# PT_2015_PB_MAIN_Rev2.net
KiCad netlist of a schematic drawn in EAGLE
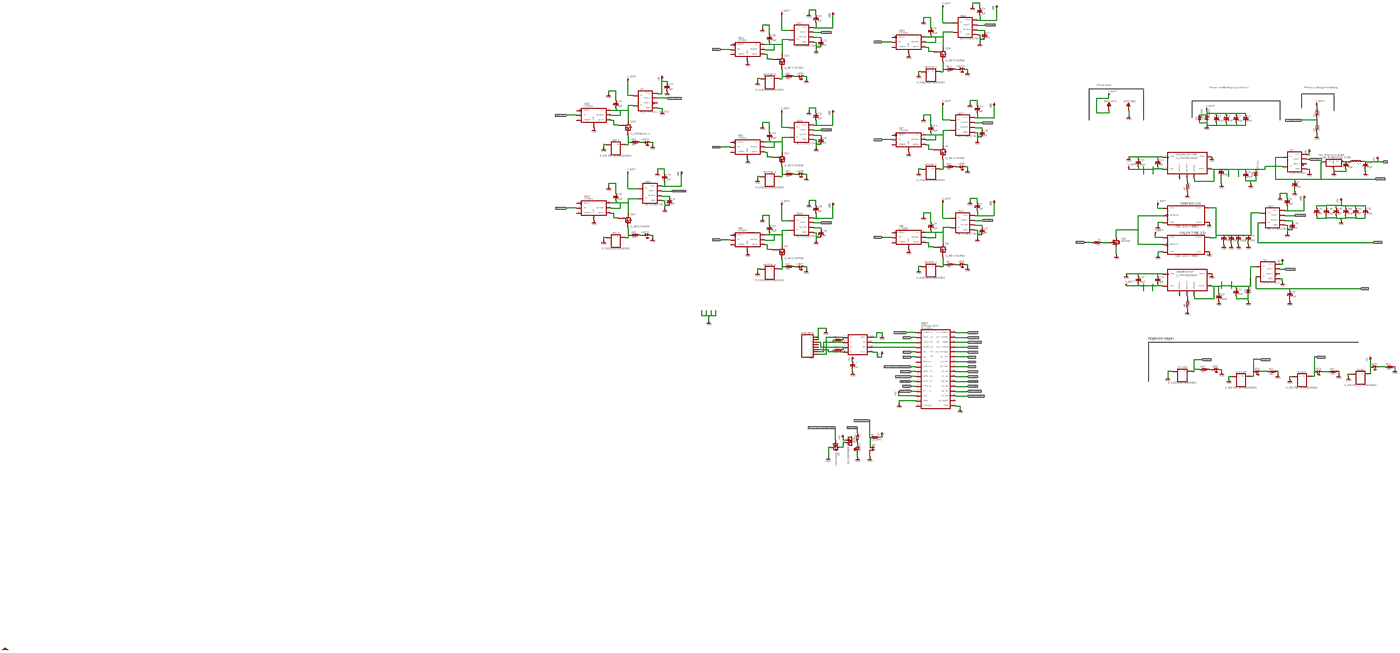
[diagram p0: schematic, sheet 1, overview]
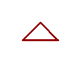
[diagram p1: schematic, sheet 1, part 1 of 5]
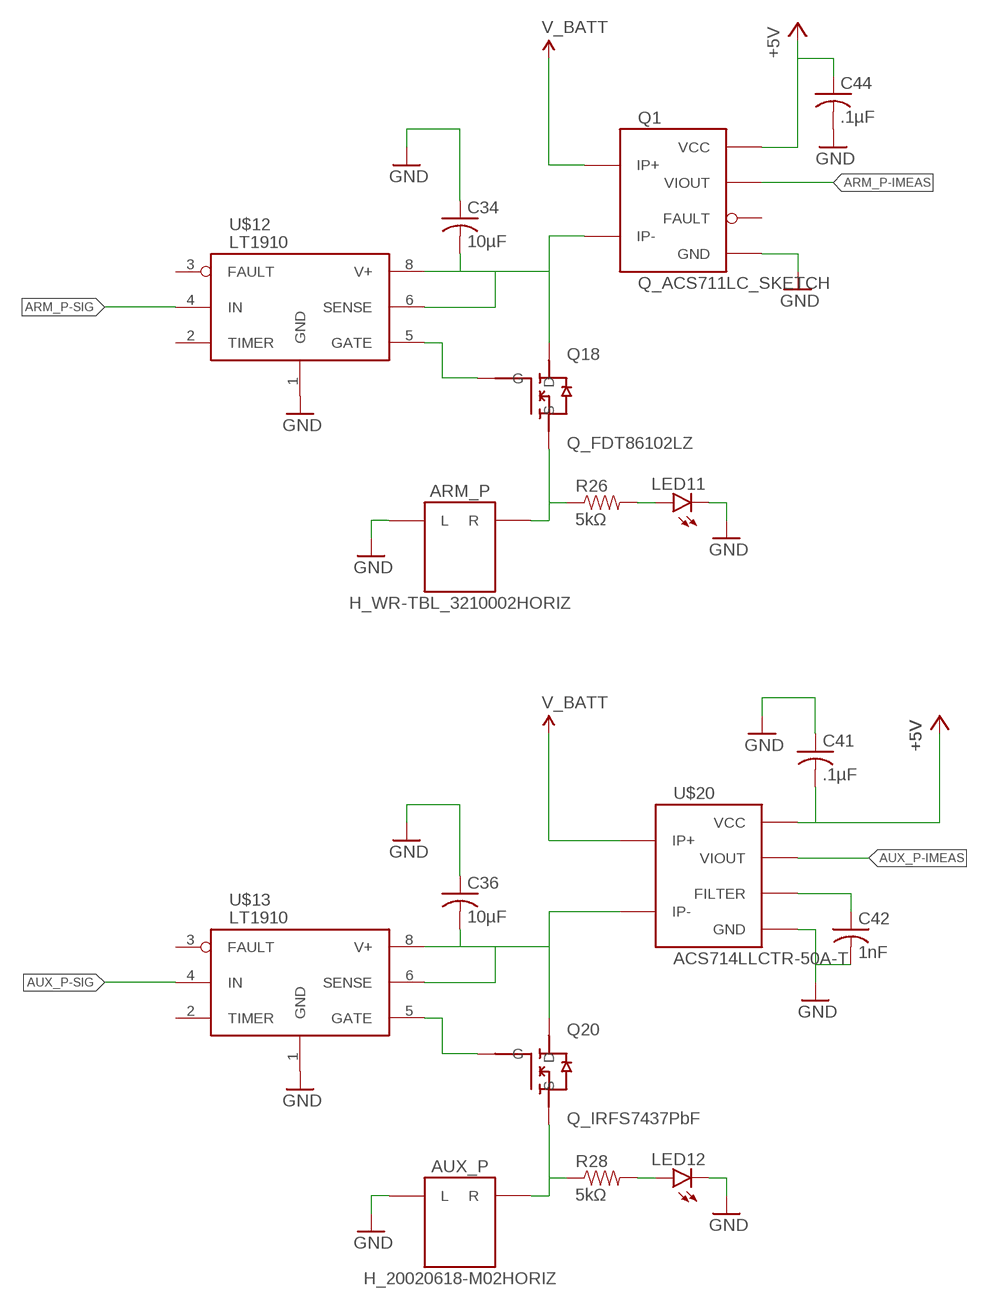
[diagram p2: schematic, sheet 1, part 2 of 5]
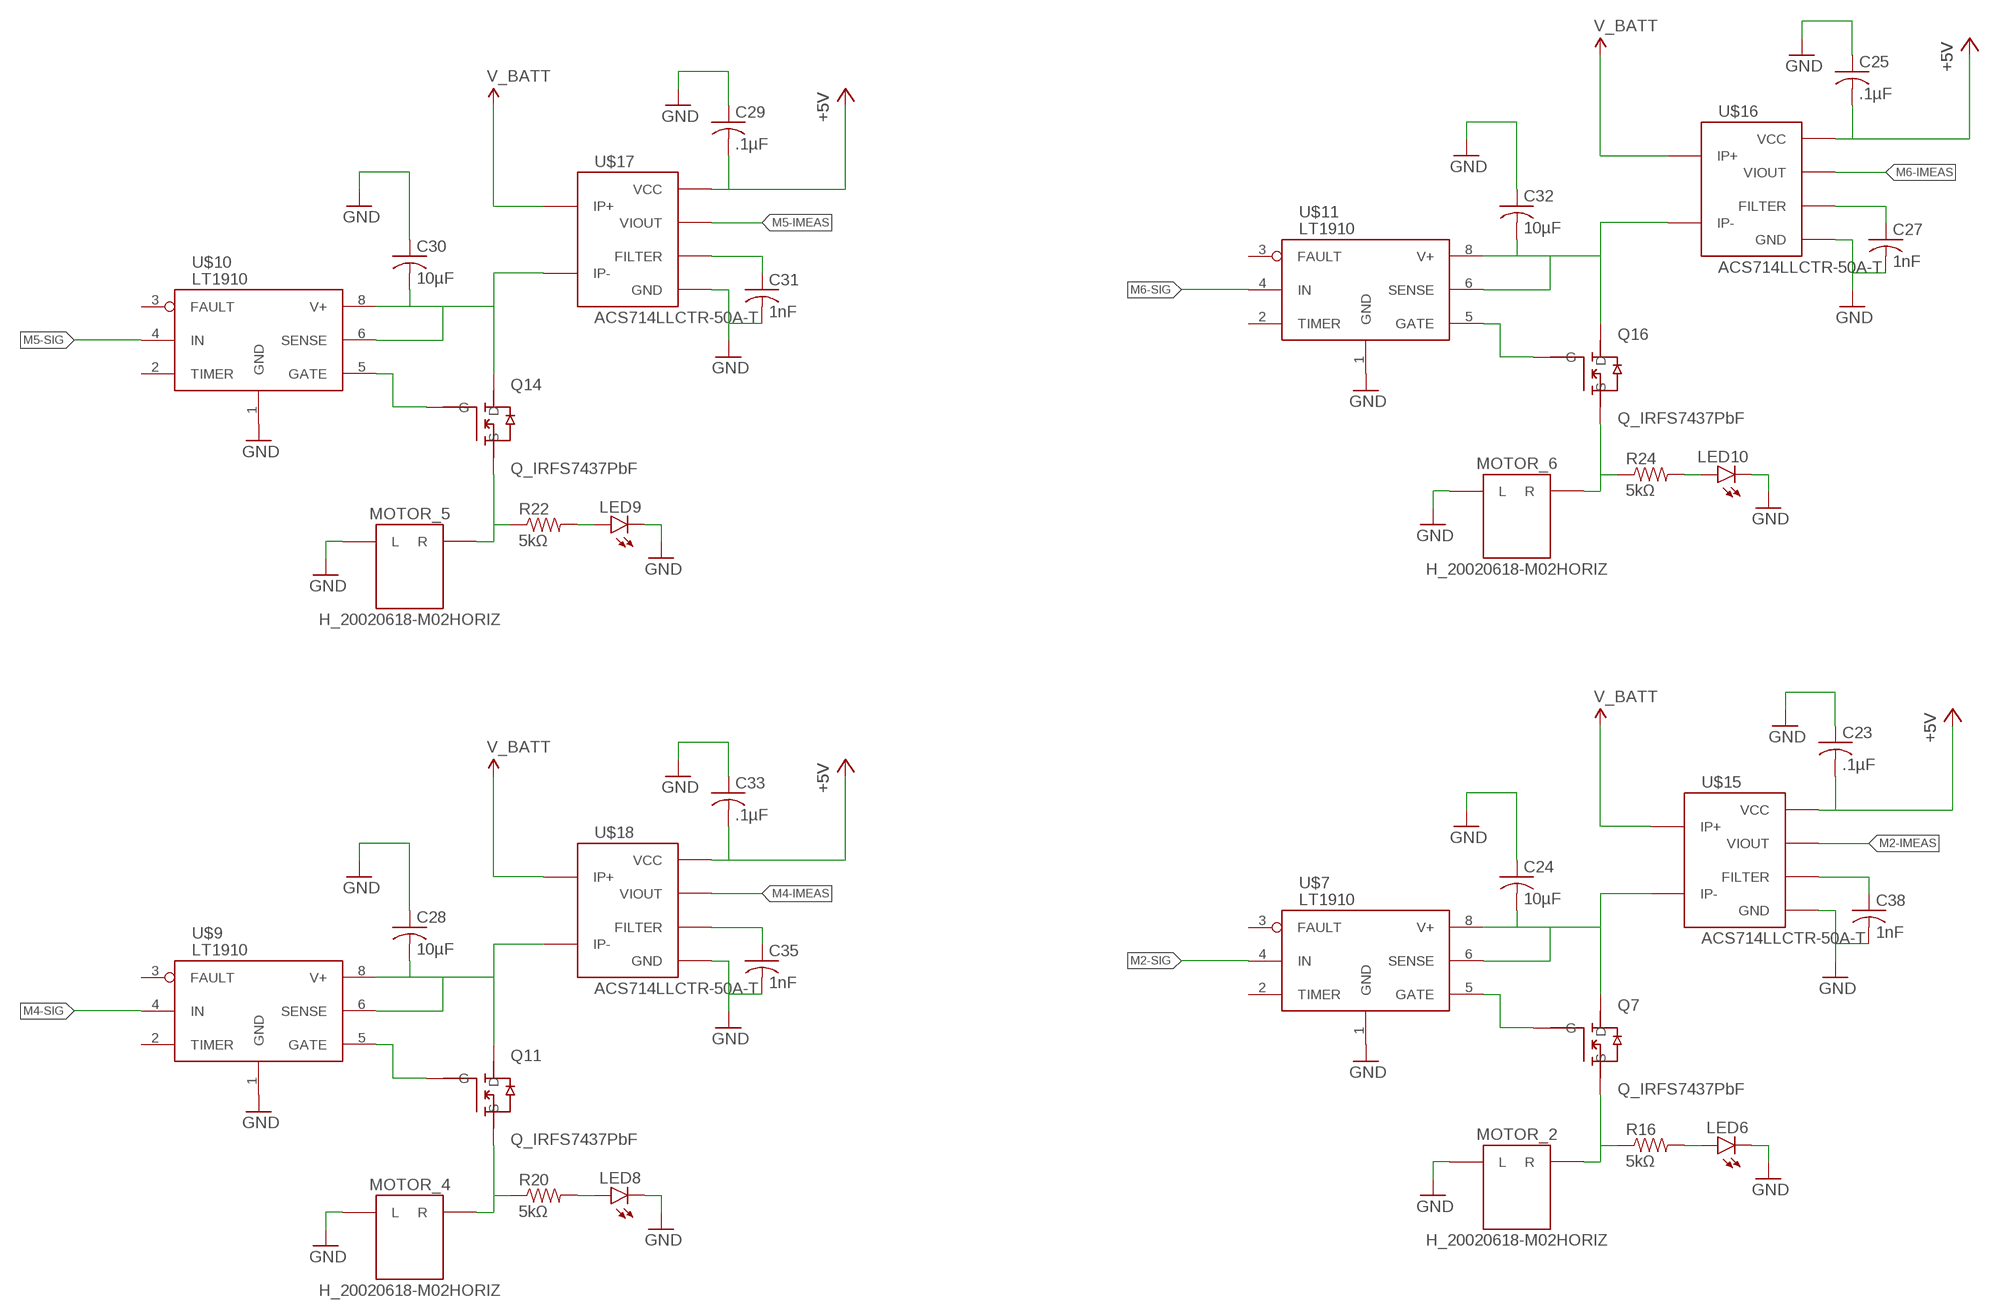
[diagram p3: schematic, sheet 1, part 3 of 5]
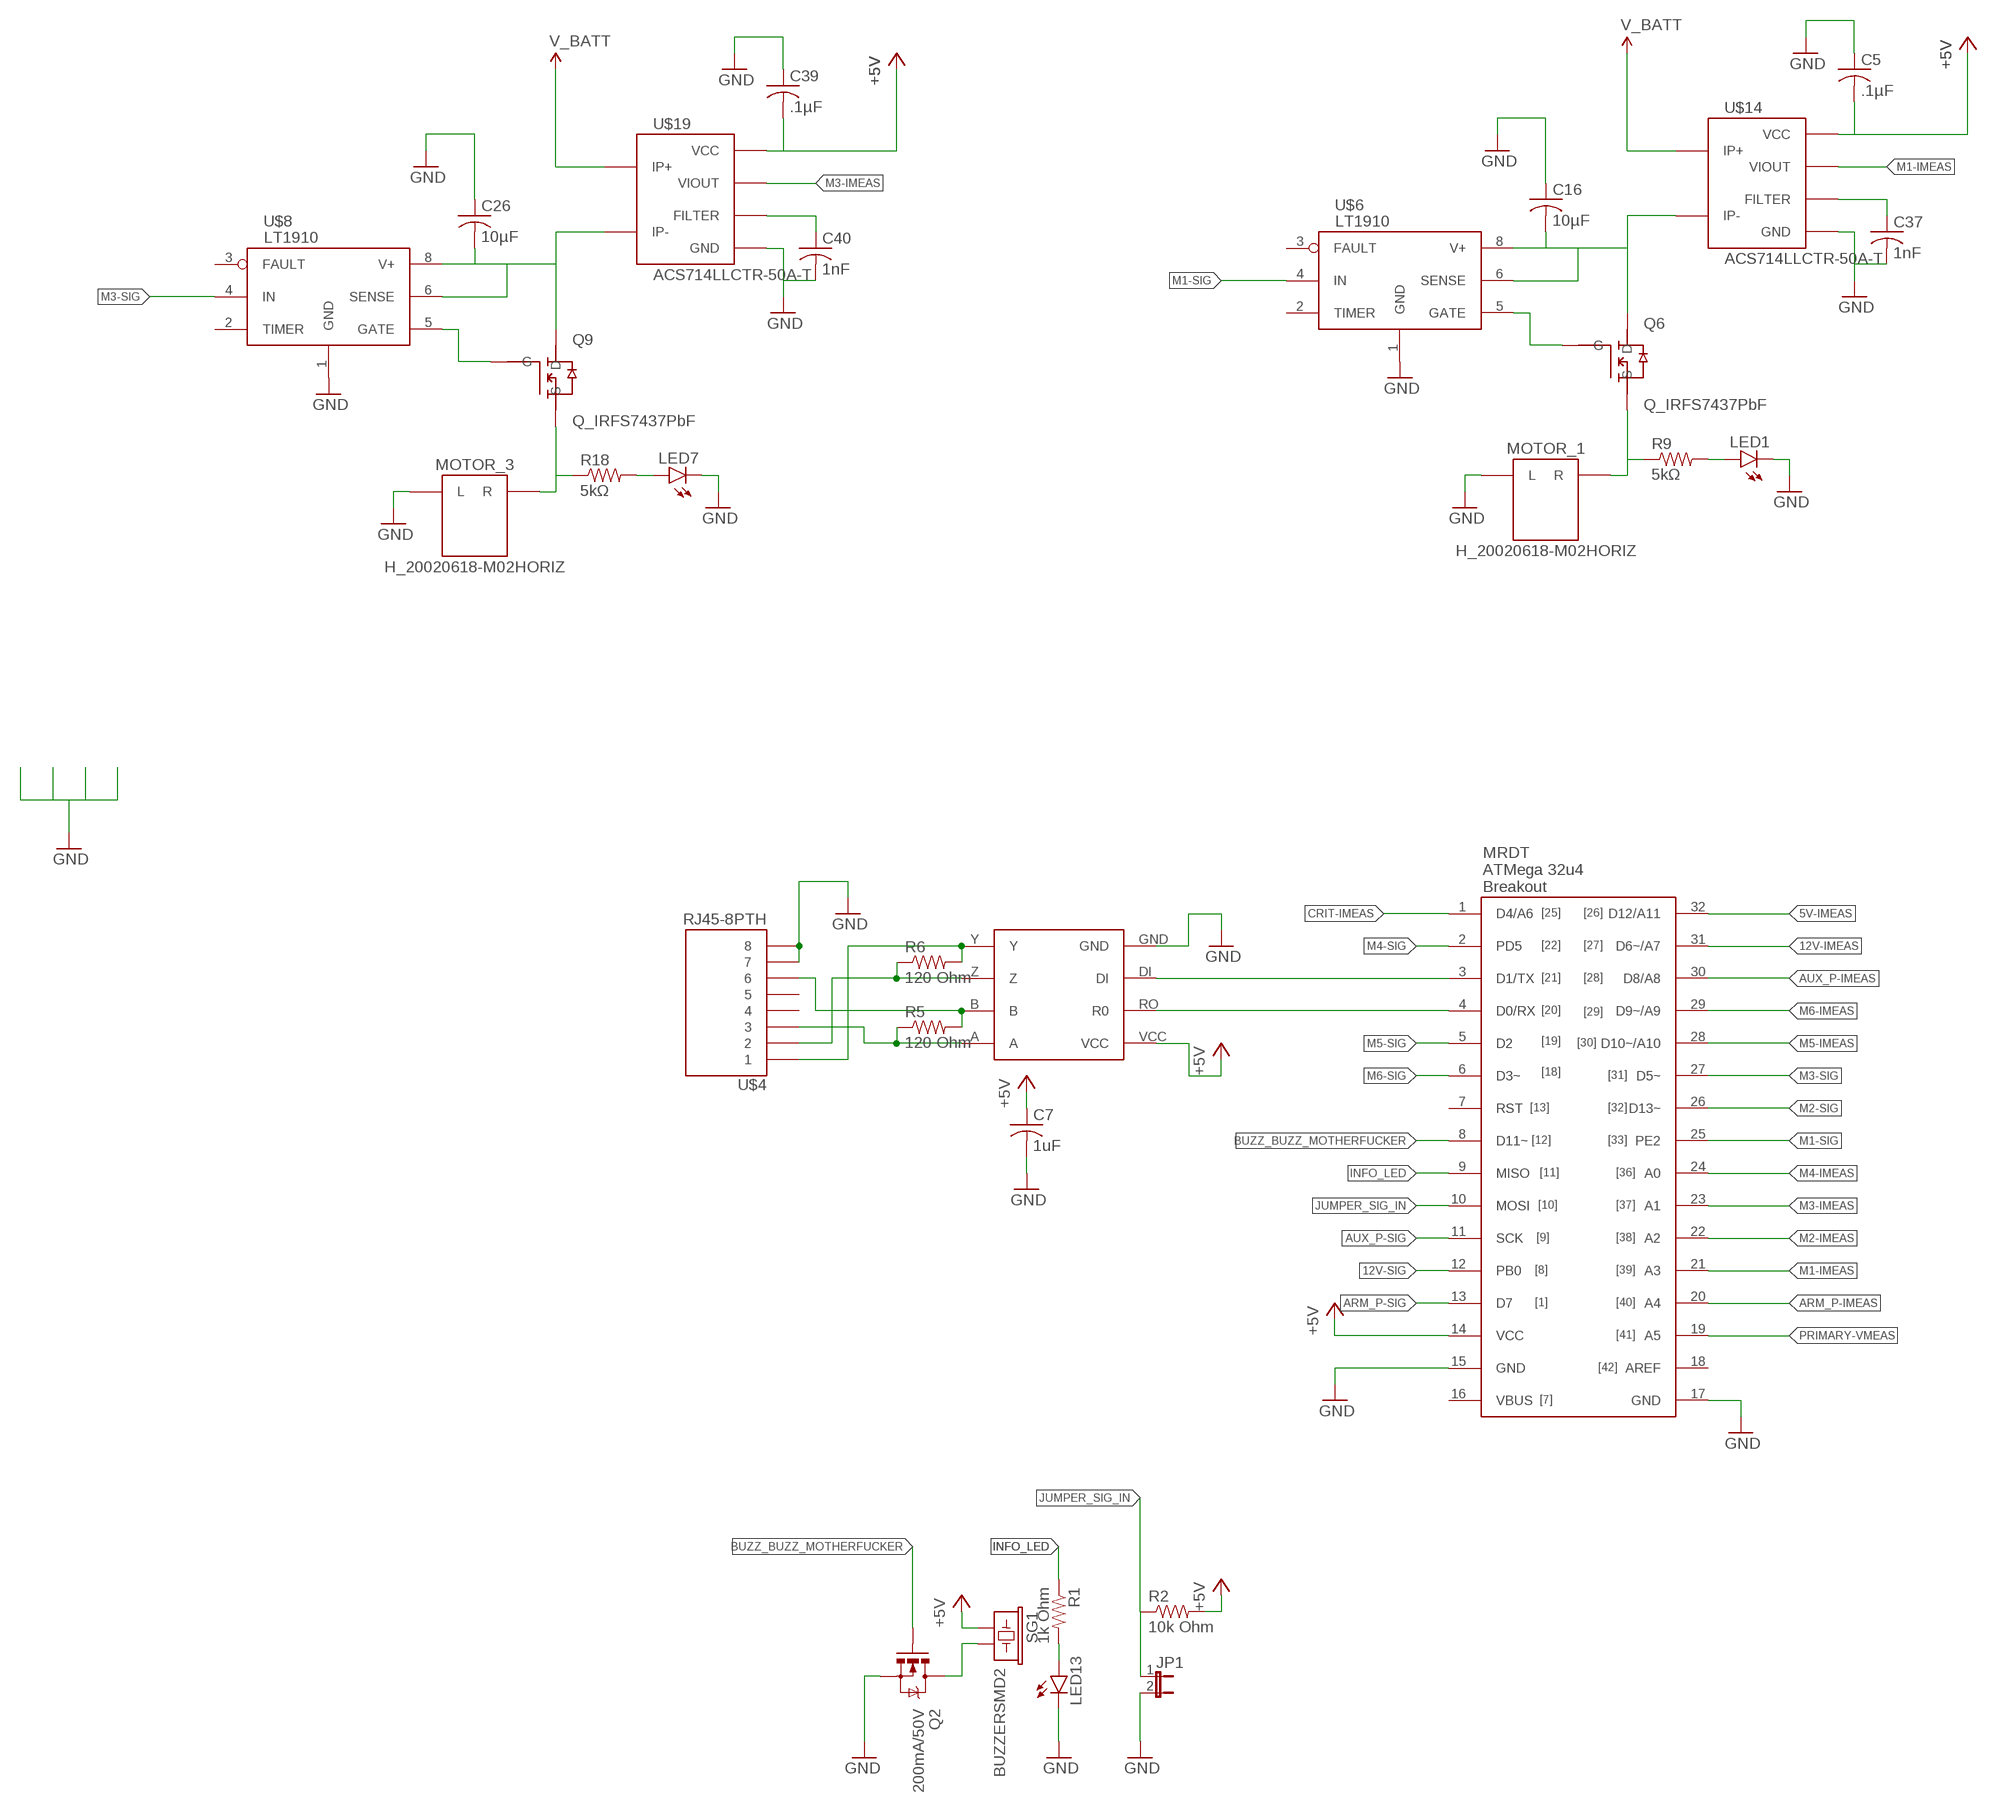
[diagram p4: schematic, sheet 1, part 4 of 5]
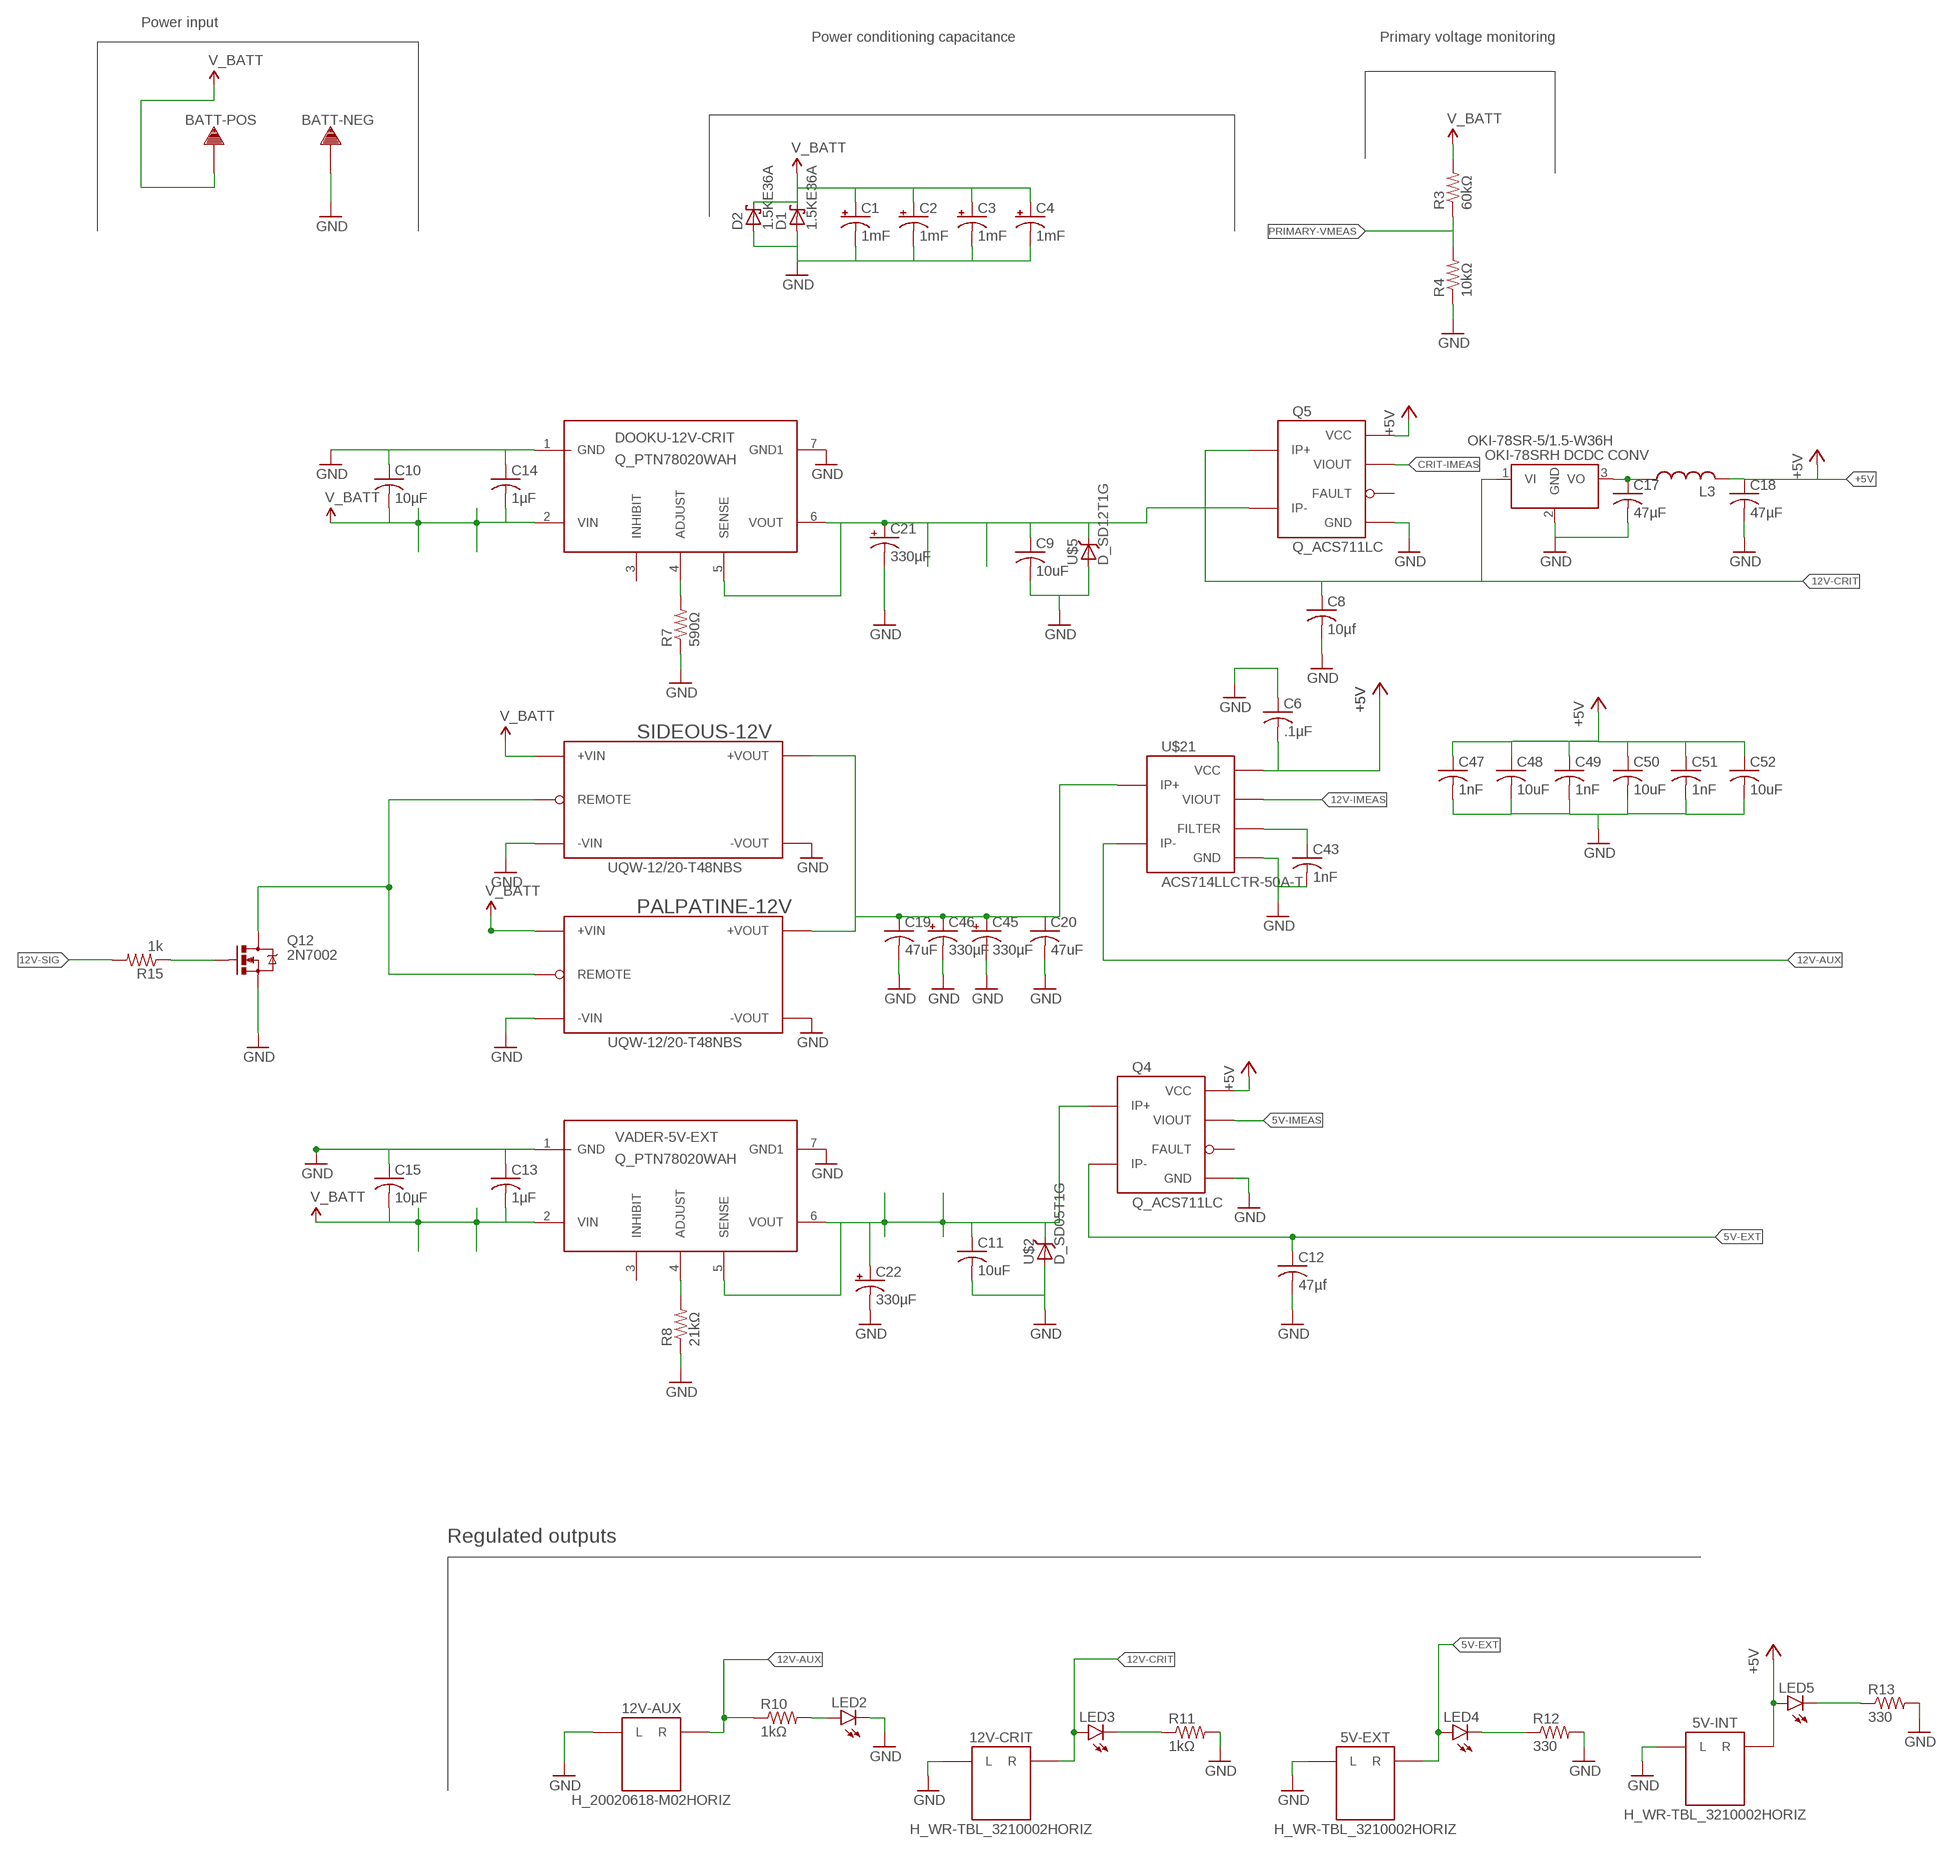
[diagram p5: schematic, sheet 1, part 5 of 5]

(export (version "E")
  (design (tool "Eeschema 10.0.6"))
  (components
    (comp (ref "5V-EXT")
      (value "H_WR-TBL_3210002HORIZ")
      (footprint "eagle-import:691322110002")
      (libsource (lib "eagle-import") (part "H_WR-TBL_3210002HORIZ"))
    )
    (comp (ref "5V-INT")
      (value "H_WR-TBL_3210002HORIZ")
      (footprint "eagle-import:691322110002")
      (libsource (lib "eagle-import") (part "H_WR-TBL_3210002HORIZ"))
    )
    (comp (ref "12V-AUX")
      (value "H_20020618-M02HORIZ")
      (footprint "eagle-import:20020618-M02")
      (libsource (lib "eagle-import") (part "H_20020618-M02HORIZ"))
    )
    (comp (ref "12V-CRIT")
      (value "H_WR-TBL_3210002HORIZ")
      (footprint "eagle-import:691322110002")
      (libsource (lib "eagle-import") (part "H_WR-TBL_3210002HORIZ"))
    )
    (comp (ref "ARM_P")
      (value "H_WR-TBL_3210002HORIZ")
      (footprint "eagle-import:691322110002")
      (libsource (lib "eagle-import") (part "H_WR-TBL_3210002HORIZ"))
    )
    (comp (ref "AUX_P")
      (value "H_20020618-M02HORIZ")
      (footprint "eagle-import:20020618-M02")
      (libsource (lib "eagle-import") (part "H_20020618-M02HORIZ"))
    )
    (comp (ref "BATT-NEG")
      (value "TERMINAL_HOLE")
      (footprint "eagle-import:LARGE_TERMINAL_HOLE")
      (libsource (lib "eagle-import") (part "TERMINAL_HOLE"))
    )
    (comp (ref "BATT-POS")
      (value "TERMINAL_HOLE")
      (footprint "eagle-import:LARGE_TERMINAL_HOLE")
      (libsource (lib "eagle-import") (part "TERMINAL_HOLE"))
    )
    (comp (ref "C1")
      (value "1mF")
      (footprint "eagle-import:C_12.5MM")
      (libsource (lib "eagle-import") (part "C_POL12.5MM_NORMAL"))
    )
    (comp (ref "C2")
      (value "1mF")
      (footprint "eagle-import:C_12.5MM")
      (libsource (lib "eagle-import") (part "C_POL12.5MM_NORMAL"))
    )
    (comp (ref "C3")
      (value "1mF")
      (footprint "eagle-import:C_12.5MM")
      (libsource (lib "eagle-import") (part "C_POL12.5MM_NORMAL"))
    )
    (comp (ref "C4")
      (value "1mF")
      (footprint "eagle-import:C_12.5MM")
      (libsource (lib "eagle-import") (part "C_POL12.5MM_NORMAL"))
    )
    (comp (ref "C5")
      (value ".1µF")
      (footprint "eagle-import:C1206")
      (libsource (lib "eagle-import") (part "C-USC1206"))
    )
    (comp (ref "C6")
      (value ".1µF")
      (footprint "eagle-import:C1206")
      (libsource (lib "eagle-import") (part "C-USC1206"))
    )
    (comp (ref "C7")
      (value "1uF")
      (footprint "eagle-import:C1206")
      (libsource (lib "eagle-import") (part "C-USC1206"))
    )
    (comp (ref "C8")
      (value "10µf")
      (footprint "eagle-import:C1206")
      (libsource (lib "eagle-import") (part "C-USC1206"))
    )
    (comp (ref "C9")
      (value "10uF")
      (footprint "eagle-import:C1206")
      (libsource (lib "eagle-import") (part "C-USC1206"))
    )
    (comp (ref "C10")
      (value "10µF")
      (footprint "eagle-import:C1206")
      (libsource (lib "eagle-import") (part "C-USC1206"))
    )
    (comp (ref "C11")
      (value "10uF")
      (footprint "eagle-import:C1206")
      (libsource (lib "eagle-import") (part "C-USC1206"))
    )
    (comp (ref "C12")
      (value "47µf")
      (footprint "eagle-import:C1206")
      (libsource (lib "eagle-import") (part "C-USC1206"))
    )
    (comp (ref "C13")
      (value "1µF")
      (footprint "eagle-import:C1206")
      (libsource (lib "eagle-import") (part "C-USC1206"))
    )
    (comp (ref "C14")
      (value "1µF")
      (footprint "eagle-import:C1206")
      (libsource (lib "eagle-import") (part "C-USC1206"))
    )
    (comp (ref "C15")
      (value "10µF")
      (footprint "eagle-import:C1206")
      (libsource (lib "eagle-import") (part "C-USC1206"))
    )
    (comp (ref "C16")
      (value "10µF")
      (footprint "eagle-import:C1206")
      (libsource (lib "eagle-import") (part "C-USC1206"))
    )
    (comp (ref "C17")
      (value "47µF")
      (footprint "eagle-import:C1206")
      (libsource (lib "eagle-import") (part "C-USC1206"))
    )
    (comp (ref "C18")
      (value "47µF")
      (footprint "eagle-import:C1206")
      (libsource (lib "eagle-import") (part "C-USC1206"))
    )
    (comp (ref "C19")
      (value "47uF")
      (footprint "eagle-import:C1206")
      (libsource (lib "eagle-import") (part "C-USC1206"))
    )
    (comp (ref "C20")
      (value "47uF")
      (footprint "eagle-import:C1206")
      (libsource (lib "eagle-import") (part "C-USC1206"))
    )
    (comp (ref "C21")
      (value "330µF")
      (footprint "eagle-import:E5-8,5")
      (libsource (lib "eagle-import") (part "CPOL-USE5-8.5"))
    )
    (comp (ref "C22")
      (value "330µF")
      (footprint "eagle-import:E5-8,5")
      (libsource (lib "eagle-import") (part "CPOL-USE5-8.5"))
    )
    (comp (ref "C23")
      (value ".1µF")
      (footprint "eagle-import:C1206")
      (libsource (lib "eagle-import") (part "C-USC1206"))
    )
    (comp (ref "C24")
      (value "10µF")
      (footprint "eagle-import:C1206")
      (libsource (lib "eagle-import") (part "C-USC1206"))
    )
    (comp (ref "C25")
      (value ".1µF")
      (footprint "eagle-import:C1206")
      (libsource (lib "eagle-import") (part "C-USC1206"))
    )
    (comp (ref "C26")
      (value "10µF")
      (footprint "eagle-import:C1206")
      (libsource (lib "eagle-import") (part "C-USC1206"))
    )
    (comp (ref "C27")
      (value "1nF")
      (footprint "eagle-import:C1206")
      (libsource (lib "eagle-import") (part "C-USC1206"))
    )
    (comp (ref "C28")
      (value "10µF")
      (footprint "eagle-import:C1206")
      (libsource (lib "eagle-import") (part "C-USC1206"))
    )
    (comp (ref "C29")
      (value ".1µF")
      (footprint "eagle-import:C1206")
      (libsource (lib "eagle-import") (part "C-USC1206"))
    )
    (comp (ref "C30")
      (value "10µF")
      (footprint "eagle-import:C1206")
      (libsource (lib "eagle-import") (part "C-USC1206"))
    )
    (comp (ref "C31")
      (value "1nF")
      (footprint "eagle-import:C1206")
      (libsource (lib "eagle-import") (part "C-USC1206"))
    )
    (comp (ref "C32")
      (value "10µF")
      (footprint "eagle-import:C1206")
      (libsource (lib "eagle-import") (part "C-USC1206"))
    )
    (comp (ref "C33")
      (value ".1µF")
      (footprint "eagle-import:C1206")
      (libsource (lib "eagle-import") (part "C-USC1206"))
    )
    (comp (ref "C34")
      (value "10µF")
      (footprint "eagle-import:C1206")
      (libsource (lib "eagle-import") (part "C-USC1206"))
    )
    (comp (ref "C35")
      (value "1nF")
      (footprint "eagle-import:C1206")
      (libsource (lib "eagle-import") (part "C-USC1206"))
    )
    (comp (ref "C36")
      (value "10µF")
      (footprint "eagle-import:C1206")
      (libsource (lib "eagle-import") (part "C-USC1206"))
    )
    (comp (ref "C37")
      (value "1nF")
      (footprint "eagle-import:C1206")
      (libsource (lib "eagle-import") (part "C-USC1206"))
    )
    (comp (ref "C38")
      (value "1nF")
      (footprint "eagle-import:C1206")
      (libsource (lib "eagle-import") (part "C-USC1206"))
    )
    (comp (ref "C39")
      (value ".1µF")
      (footprint "eagle-import:C1206")
      (libsource (lib "eagle-import") (part "C-USC1206"))
    )
    (comp (ref "C40")
      (value "1nF")
      (footprint "eagle-import:C1206")
      (libsource (lib "eagle-import") (part "C-USC1206"))
    )
    (comp (ref "C41")
      (value ".1µF")
      (footprint "eagle-import:C1206")
      (libsource (lib "eagle-import") (part "C-USC1206"))
    )
    (comp (ref "C42")
      (value "1nF")
      (footprint "eagle-import:C1206")
      (libsource (lib "eagle-import") (part "C-USC1206"))
    )
    (comp (ref "C43")
      (value "1nF")
      (footprint "eagle-import:C1206")
      (libsource (lib "eagle-import") (part "C-USC1206"))
    )
    (comp (ref "C44")
      (value ".1µF")
      (footprint "eagle-import:C1206")
      (libsource (lib "eagle-import") (part "C-USC1206"))
    )
    (comp (ref "C45")
      (value "330µF")
      (footprint "eagle-import:E5-8,5")
      (libsource (lib "eagle-import") (part "CPOL-USE5-8.5"))
    )
    (comp (ref "C46")
      (value "330µF")
      (footprint "eagle-import:E5-8,5")
      (libsource (lib "eagle-import") (part "CPOL-USE5-8.5"))
    )
    (comp (ref "C47")
      (value "1nF")
      (footprint "eagle-import:C1206")
      (libsource (lib "eagle-import") (part "C-USC1206"))
    )
    (comp (ref "C48")
      (value "10uF")
      (footprint "eagle-import:C1206")
      (libsource (lib "eagle-import") (part "C-USC1206"))
    )
    (comp (ref "C49")
      (value "1nF")
      (footprint "eagle-import:C1206")
      (libsource (lib "eagle-import") (part "C-USC1206"))
    )
    (comp (ref "C50")
      (value "10uF")
      (footprint "eagle-import:C1206")
      (libsource (lib "eagle-import") (part "C-USC1206"))
    )
    (comp (ref "C51")
      (value "1nF")
      (footprint "eagle-import:C1206")
      (libsource (lib "eagle-import") (part "C-USC1206"))
    )
    (comp (ref "C52")
      (value "10uF")
      (footprint "eagle-import:C1206")
      (libsource (lib "eagle-import") (part "C-USC1206"))
    )
    (comp (ref "D1")
      (value "1.5KE36A")
      (footprint "eagle-import:CB429-17")
      (libsource (lib "eagle-import") (part "15KEXX"))
    )
    (comp (ref "D2")
      (value "1.5KE36A")
      (footprint "eagle-import:CB429-17")
      (libsource (lib "eagle-import") (part "15KEXX"))
    )
    (comp (ref "DOOKU-12V-CRIT")
      (value "Q_PTN78020WAH")
      (footprint "eagle-import:R_PDSS-T7")
      (libsource (lib "eagle-import") (part "Q_PTN78020"))
    )
    (comp (ref "JP1")
      (value "JP1E")
      (footprint "eagle-import:JP1")
      (libsource (lib "eagle-import") (part "JP1E"))
    )
    (comp (ref "L3")
      (value "L-USL8530M")
      (footprint "eagle-import:L8530M")
      (libsource (lib "eagle-import") (part "L-USL8530M"))
    )
    (comp (ref "LED1")
      (value "LED1206")
      (footprint "eagle-import:LED-1206")
      (libsource (lib "eagle-import") (part "LED1206"))
    )
    (comp (ref "LED2")
      (value "LED1206")
      (footprint "eagle-import:LED-1206")
      (libsource (lib "eagle-import") (part "LED1206"))
    )
    (comp (ref "LED3")
      (value "LED1206")
      (footprint "eagle-import:LED-1206")
      (libsource (lib "eagle-import") (part "LED1206"))
    )
    (comp (ref "LED4")
      (value "LED1206")
      (footprint "eagle-import:LED-1206")
      (libsource (lib "eagle-import") (part "LED1206"))
    )
    (comp (ref "LED5")
      (value "LED1206")
      (footprint "eagle-import:LED-1206")
      (libsource (lib "eagle-import") (part "LED1206"))
    )
    (comp (ref "LED6")
      (value "LED1206")
      (footprint "eagle-import:LED-1206")
      (libsource (lib "eagle-import") (part "LED1206"))
    )
    (comp (ref "LED7")
      (value "LED1206")
      (footprint "eagle-import:LED-1206")
      (libsource (lib "eagle-import") (part "LED1206"))
    )
    (comp (ref "LED8")
      (value "LED1206")
      (footprint "eagle-import:LED-1206")
      (libsource (lib "eagle-import") (part "LED1206"))
    )
    (comp (ref "LED9")
      (value "LED1206")
      (footprint "eagle-import:LED-1206")
      (libsource (lib "eagle-import") (part "LED1206"))
    )
    (comp (ref "LED10")
      (value "LED1206")
      (footprint "eagle-import:LED-1206")
      (libsource (lib "eagle-import") (part "LED1206"))
    )
    (comp (ref "LED11")
      (value "LED1206")
      (footprint "eagle-import:LED-1206")
      (libsource (lib "eagle-import") (part "LED1206"))
    )
    (comp (ref "LED12")
      (value "LED1206")
      (footprint "eagle-import:LED-1206")
      (libsource (lib "eagle-import") (part "LED1206"))
    )
    (comp (ref "LED13")
      (value "LED-FKIT-1206")
      (footprint "eagle-import:FKIT-LED-1206")
      (libsource (lib "eagle-import") (part "LED-FKIT-1206"))
    )
    (comp (ref "MOTOR_1")
      (value "H_20020618-M02HORIZ")
      (footprint "eagle-import:20020618-M02")
      (libsource (lib "eagle-import") (part "H_20020618-M02HORIZ"))
    )
    (comp (ref "MOTOR_2")
      (value "H_20020618-M02HORIZ")
      (footprint "eagle-import:20020618-M02")
      (libsource (lib "eagle-import") (part "H_20020618-M02HORIZ"))
    )
    (comp (ref "MOTOR_3")
      (value "H_20020618-M02HORIZ")
      (footprint "eagle-import:20020618-M02")
      (libsource (lib "eagle-import") (part "H_20020618-M02HORIZ"))
    )
    (comp (ref "MOTOR_4")
      (value "H_20020618-M02HORIZ")
      (footprint "eagle-import:20020618-M02")
      (libsource (lib "eagle-import") (part "H_20020618-M02HORIZ"))
    )
    (comp (ref "MOTOR_5")
      (value "H_20020618-M02HORIZ")
      (footprint "eagle-import:20020618-M02")
      (libsource (lib "eagle-import") (part "H_20020618-M02HORIZ"))
    )
    (comp (ref "MOTOR_6")
      (value "H_20020618-M02HORIZ")
      (footprint "eagle-import:20020618-M02")
      (libsource (lib "eagle-import") (part "H_20020618-M02HORIZ"))
    )
    (comp (ref "OKI-78SR-5/1.5-W36H")
      (value "Q_OKI-78SR")
      (footprint "eagle-import:OKI-78SRH")
      (libsource (lib "eagle-import") (part "Q_OKI-78SR"))
    )
    (comp (ref "PALPATINE-12V")
      (value "UQW-12/20-T48NBS")
      (footprint "eagle-import:U-T48-QB-NO_TRIM")
      (libsource (lib "eagle-import") (part "UQW-12/20-T48NBS"))
    )
    (comp (ref "Q1")
      (value "Q_ACS711LC_SKETCH")
      (footprint "eagle-import:SOIC8_ACS711_SKETCH")
      (libsource (lib "eagle-import") (part "Q_ACS711LC_SKETCH"))
    )
    (comp (ref "Q2")
      (value "200mA/50V")
      (footprint "eagle-import:SOT23-3")
      (libsource (lib "eagle-import") (part "MOSFET-NCHANNELBSS138"))
    )
    (comp (ref "Q4")
      (value "Q_ACS711LC")
      (footprint "eagle-import:SOIC8_ACS711")
      (libsource (lib "eagle-import") (part "Q_ACS711LC"))
    )
    (comp (ref "Q5")
      (value "Q_ACS711LC")
      (footprint "eagle-import:SOIC8_ACS711")
      (libsource (lib "eagle-import") (part "Q_ACS711LC"))
    )
    (comp (ref "Q6")
      (value "Q_IRFS7437PbF")
      (footprint "eagle-import:D2PACK")
      (libsource (lib "eagle-import") (part "Q_IRF7437SMD"))
    )
    (comp (ref "Q7")
      (value "Q_IRFS7437PbF")
      (footprint "eagle-import:D2PACK")
      (libsource (lib "eagle-import") (part "Q_IRF7437SMD"))
    )
    (comp (ref "Q9")
      (value "Q_IRFS7437PbF")
      (footprint "eagle-import:D2PACK")
      (libsource (lib "eagle-import") (part "Q_IRF7437SMD"))
    )
    (comp (ref "Q11")
      (value "Q_IRFS7437PbF")
      (footprint "eagle-import:D2PACK")
      (libsource (lib "eagle-import") (part "Q_IRF7437SMD"))
    )
    (comp (ref "Q12")
      (value "2N7002")
      (footprint "eagle-import:SOT323")
      (libsource (lib "eagle-import") (part "MOSFET-NCHANNEL2N7002PW"))
    )
    (comp (ref "Q14")
      (value "Q_IRFS7437PbF")
      (footprint "eagle-import:D2PACK")
      (libsource (lib "eagle-import") (part "Q_IRF7437SMD"))
    )
    (comp (ref "Q16")
      (value "Q_IRFS7437PbF")
      (footprint "eagle-import:D2PACK")
      (libsource (lib "eagle-import") (part "Q_IRF7437SMD"))
    )
    (comp (ref "Q18")
      (value "Q_FDT86102LZ")
      (footprint "eagle-import:SOT-223")
      (libsource (lib "eagle-import") (part "Q_FDT86102LZ"))
    )
    (comp (ref "Q20")
      (value "Q_IRFS7437PbF")
      (footprint "eagle-import:D2PACK")
      (libsource (lib "eagle-import") (part "Q_IRF7437SMD"))
    )
    (comp (ref "R1")
      (value "1k Ohm")
      (footprint "eagle-import:1206")
      (libsource (lib "eagle-import") (part "RESISTOR1206"))
    )
    (comp (ref "R2")
      (value "10k Ohm")
      (footprint "eagle-import:1206")
      (libsource (lib "eagle-import") (part "RESISTOR1206"))
    )
    (comp (ref "R3")
      (value "60kΩ")
      (footprint "eagle-import:R1206")
      (libsource (lib "eagle-import") (part "R-US_R1206"))
    )
    (comp (ref "R4")
      (value "10kΩ")
      (footprint "eagle-import:R1206")
      (libsource (lib "eagle-import") (part "R-US_R1206"))
    )
    (comp (ref "R5")
      (value "120 Ohm")
      (footprint "eagle-import:1206")
      (libsource (lib "eagle-import") (part "RESISTOR1206"))
    )
    (comp (ref "R6")
      (value "120 Ohm")
      (footprint "eagle-import:1206")
      (libsource (lib "eagle-import") (part "RESISTOR1206"))
    )
    (comp (ref "R7")
      (value "590Ω")
      (footprint "eagle-import:R1206")
      (libsource (lib "eagle-import") (part "R-US_R1206"))
    )
    (comp (ref "R8")
      (value "21kΩ")
      (footprint "eagle-import:R1206")
      (libsource (lib "eagle-import") (part "R-US_R1206"))
    )
    (comp (ref "R9")
      (value "5kΩ")
      (footprint "eagle-import:1206")
      (libsource (lib "eagle-import") (part "RESISTOR1206"))
    )
    (comp (ref "R10")
      (value "1kΩ")
      (footprint "eagle-import:1206")
      (libsource (lib "eagle-import") (part "RESISTOR1206"))
    )
    (comp (ref "R11")
      (value "1kΩ")
      (footprint "eagle-import:1206")
      (libsource (lib "eagle-import") (part "RESISTOR1206"))
    )
    (comp (ref "R12")
      (value "330")
      (footprint "eagle-import:1206")
      (libsource (lib "eagle-import") (part "RESISTOR1206"))
    )
    (comp (ref "R13")
      (value "330")
      (footprint "eagle-import:1206")
      (libsource (lib "eagle-import") (part "RESISTOR1206"))
    )
    (comp (ref "R15")
      (value "1k")
      (footprint "eagle-import:R1206")
      (libsource (lib "eagle-import") (part "R-US_R1206"))
    )
    (comp (ref "R16")
      (value "5kΩ")
      (footprint "eagle-import:1206")
      (libsource (lib "eagle-import") (part "RESISTOR1206"))
    )
    (comp (ref "R18")
      (value "5kΩ")
      (footprint "eagle-import:1206")
      (libsource (lib "eagle-import") (part "RESISTOR1206"))
    )
    (comp (ref "R20")
      (value "5kΩ")
      (footprint "eagle-import:1206")
      (libsource (lib "eagle-import") (part "RESISTOR1206"))
    )
    (comp (ref "R22")
      (value "5kΩ")
      (footprint "eagle-import:1206")
      (libsource (lib "eagle-import") (part "RESISTOR1206"))
    )
    (comp (ref "R24")
      (value "5kΩ")
      (footprint "eagle-import:1206")
      (libsource (lib "eagle-import") (part "RESISTOR1206"))
    )
    (comp (ref "R26")
      (value "5kΩ")
      (footprint "eagle-import:1206")
      (libsource (lib "eagle-import") (part "RESISTOR1206"))
    )
    (comp (ref "R28")
      (value "5kΩ")
      (footprint "eagle-import:1206")
      (libsource (lib "eagle-import") (part "RESISTOR1206"))
    )
    (comp (ref "SG1")
      (value "BUZZERSMD2")
      (footprint "eagle-import:BUZZER-CCV")
      (libsource (lib "eagle-import") (part "BUZZERSMD2"))
    )
    (comp (ref "SIDEOUS-12V")
      (value "UQW-12/20-T48NBS")
      (footprint "eagle-import:U-T48-QB-NO_TRIM")
      (libsource (lib "eagle-import") (part "UQW-12/20-T48NBS"))
    )
    (comp (ref "U$1")
      (value "32U4_BREAKOUT")
      (footprint "eagle-import:32U4_MCU_DIP")
      (libsource (lib "eagle-import") (part "32U4_BREAKOUT"))
    )
    (comp (ref "U$2")
      (value "D_SD05T1G")
      (footprint "eagle-import:SOD-323")
      (libsource (lib "eagle-import") (part "D_SD12T1G"))
    )
    (comp (ref "U$3")
      (value "MAX3077")
      (footprint "eagle-import:MAX3070E")
      (libsource (lib "eagle-import") (part "MAX3077"))
    )
    (comp (ref "U$4")
      (value "RJ45-8PTH")
      (footprint "eagle-import:RJ45-8")
      (libsource (lib "eagle-import") (part "RJ45-8PTH"))
    )
    (comp (ref "U$5")
      (value "D_SD12T1G")
      (footprint "eagle-import:SOD-323")
      (libsource (lib "eagle-import") (part "D_SD12T1G"))
    )
    (comp (ref "U$6")
      (value "LT1910")
      (footprint "eagle-import:SO8")
      (libsource (lib "eagle-import") (part "LT1910"))
    )
    (comp (ref "U$7")
      (value "LT1910")
      (footprint "eagle-import:SO8")
      (libsource (lib "eagle-import") (part "LT1910"))
    )
    (comp (ref "U$8")
      (value "LT1910")
      (footprint "eagle-import:SO8")
      (libsource (lib "eagle-import") (part "LT1910"))
    )
    (comp (ref "U$9")
      (value "LT1910")
      (footprint "eagle-import:SO8")
      (libsource (lib "eagle-import") (part "LT1910"))
    )
    (comp (ref "U$10")
      (value "LT1910")
      (footprint "eagle-import:SO8")
      (libsource (lib "eagle-import") (part "LT1910"))
    )
    (comp (ref "U$11")
      (value "LT1910")
      (footprint "eagle-import:SO8")
      (libsource (lib "eagle-import") (part "LT1910"))
    )
    (comp (ref "U$12")
      (value "LT1910")
      (footprint "eagle-import:SO8")
      (libsource (lib "eagle-import") (part "LT1910"))
    )
    (comp (ref "U$13")
      (value "LT1910")
      (footprint "eagle-import:SO8")
      (libsource (lib "eagle-import") (part "LT1910"))
    )
    (comp (ref "U$14")
      (value "ACS714LLCTR-50A-T")
      (footprint "eagle-import:SOIC8_ACS711_SKETCH")
      (libsource (lib "eagle-import") (part "Q_ACS714_SKETCH"))
    )
    (comp (ref "U$15")
      (value "ACS714LLCTR-50A-T")
      (footprint "eagle-import:SOIC8_ACS711_SKETCH")
      (libsource (lib "eagle-import") (part "Q_ACS714_SKETCH"))
    )
    (comp (ref "U$16")
      (value "ACS714LLCTR-50A-T")
      (footprint "eagle-import:SOIC8_ACS711_SKETCH")
      (libsource (lib "eagle-import") (part "Q_ACS714_SKETCH"))
    )
    (comp (ref "U$17")
      (value "ACS714LLCTR-50A-T")
      (footprint "eagle-import:SOIC8_ACS711_SKETCH")
      (libsource (lib "eagle-import") (part "Q_ACS714_SKETCH"))
    )
    (comp (ref "U$18")
      (value "ACS714LLCTR-50A-T")
      (footprint "eagle-import:SOIC8_ACS711_SKETCH")
      (libsource (lib "eagle-import") (part "Q_ACS714_SKETCH"))
    )
    (comp (ref "U$19")
      (value "ACS714LLCTR-50A-T")
      (footprint "eagle-import:SOIC8_ACS711_SKETCH")
      (libsource (lib "eagle-import") (part "Q_ACS714_SKETCH"))
    )
    (comp (ref "U$20")
      (value "ACS714LLCTR-50A-T")
      (footprint "eagle-import:SOIC8_ACS711_SKETCH")
      (libsource (lib "eagle-import") (part "Q_ACS714_SKETCH"))
    )
    (comp (ref "U$21")
      (value "ACS714LLCTR-50A-T")
      (footprint "eagle-import:SOIC8_ACS711")
      (libsource (lib "eagle-import") (part "Q_ACS714"))
    )
    (comp (ref "U$22")
      (value "TEST")
      (footprint "eagle-import:TEST")
      (libsource (lib "eagle-import") (part "TEST"))
    )
    (comp (ref "VADER-5V-EXT")
      (value "Q_PTN78020WAH")
      (footprint "eagle-import:R_PDSS-T7")
      (libsource (lib "eagle-import") (part "Q_PTN78020"))
    )
  )
  (nets
    (net (code "1") (name "+5V") (class "Default")
      (node (ref "5V-INT") (pin "R") (pinfunction "R_R") (pintype "bidirectional"))
      (node (ref "C18") (pin "1") (pinfunction "1_1") (pintype "passive"))
      (node (ref "C23") (pin "2") (pinfunction "2_2") (pintype "passive"))
      (node (ref "C25") (pin "2") (pinfunction "2_2") (pintype "passive"))
      (node (ref "C29") (pin "2") (pinfunction "2_2") (pintype "passive"))
      (node (ref "C33") (pin "2") (pinfunction "2_2") (pintype "passive"))
      (node (ref "C39") (pin "2") (pinfunction "2_2") (pintype "passive"))
      (node (ref "C41") (pin "2") (pinfunction "2_2") (pintype "passive"))
      (node (ref "C44") (pin "1") (pinfunction "1_1") (pintype "passive"))
      (node (ref "C47") (pin "1") (pinfunction "1_1") (pintype "passive"))
      (node (ref "C48") (pin "1") (pinfunction "1_1") (pintype "passive"))
      (node (ref "C49") (pin "1") (pinfunction "1_1") (pintype "passive"))
      (node (ref "C5") (pin "2") (pinfunction "2_2") (pintype "passive"))
      (node (ref "C50") (pin "1") (pinfunction "1_1") (pintype "passive"))
      (node (ref "C51") (pin "1") (pinfunction "1_1") (pintype "passive"))
      (node (ref "C52") (pin "1") (pinfunction "1_1") (pintype "passive"))
      (node (ref "C6") (pin "2") (pinfunction "2_2") (pintype "passive"))
      (node (ref "C7") (pin "1") (pinfunction "1_1") (pintype "passive"))
      (node (ref "L3") (pin "2") (pinfunction "2_2") (pintype "passive"))
      (node (ref "LED5") (pin "A") (pinfunction "A_A") (pintype "passive"))
      (node (ref "Q1") (pin "8") (pinfunction "VCC_8") (pintype "bidirectional"))
      (node (ref "Q4") (pin "8") (pinfunction "VCC_8") (pintype "bidirectional"))
      (node (ref "Q5") (pin "8") (pinfunction "VCC_8") (pintype "bidirectional"))
      (node (ref "R2") (pin "2") (pinfunction "2_2") (pintype "passive"))
      (node (ref "SG1") (pin "+") (pinfunction "1_+") (pintype "passive"))
      (node (ref "U$1") (pin "14") (pinfunction "VCC_14") (pintype "bidirectional"))
      (node (ref "U$14") (pin "8") (pinfunction "VCC_8") (pintype "bidirectional"))
      (node (ref "U$15") (pin "8") (pinfunction "VCC_8") (pintype "bidirectional"))
      (node (ref "U$16") (pin "8") (pinfunction "VCC_8") (pintype "bidirectional"))
      (node (ref "U$17") (pin "8") (pinfunction "VCC_8") (pintype "bidirectional"))
      (node (ref "U$18") (pin "8") (pinfunction "VCC_8") (pintype "bidirectional"))
      (node (ref "U$19") (pin "8") (pinfunction "VCC_8") (pintype "bidirectional"))
      (node (ref "U$20") (pin "8") (pinfunction "VCC_8") (pintype "bidirectional"))
      (node (ref "U$21") (pin "8") (pinfunction "VCC_8") (pintype "bidirectional"))
      (node (ref "U$3") (pin "VCC") (pinfunction "VCC_VCC") (pintype "bidirectional"))
    )
    (net (code "2") (name "5V-EXT") (class "Default")
      (node (ref "5V-EXT") (pin "R") (pinfunction "R_R") (pintype "bidirectional"))
      (node (ref "C12") (pin "1") (pinfunction "1_1") (pintype "passive"))
      (node (ref "LED4") (pin "A") (pinfunction "A_A") (pintype "passive"))
      (node (ref "Q4") (pin "4") (pinfunction "IP-_4") (pintype "bidirectional"))
    )
    (net (code "3") (name "5V-IMEAS") (class "Default")
      (node (ref "Q4") (pin "7") (pinfunction "VIOUT_7") (pintype "bidirectional"))
      (node (ref "U$1") (pin "32") (pinfunction "D12/A11_32") (pintype "bidirectional"))
    )
    (net (code "4") (name "12V-AUX") (class "Default")
      (node (ref "12V-AUX") (pin "R1") (pinfunction "R_R1") (pintype "bidirectional"))
      (node (ref "12V-AUX") (pin "R2") (pinfunction "R_R2") (pintype "bidirectional"))
      (node (ref "R10") (pin "1") (pinfunction "1_1") (pintype "passive"))
      (node (ref "U$21") (pin "4") (pinfunction "IP-_4") (pintype "bidirectional"))
    )
    (net (code "5") (name "12V-CRIT") (class "Default")
      (node (ref "12V-CRIT") (pin "R") (pinfunction "R_R") (pintype "bidirectional"))
      (node (ref "C8") (pin "1") (pinfunction "1_1") (pintype "passive"))
      (node (ref "LED3") (pin "A") (pinfunction "A_A") (pintype "passive"))
      (node (ref "OKI-78SR-5/1.5-W36H") (pin "1") (pinfunction "VI_1") (pintype "bidirectional"))
      (node (ref "Q5") (pin "1") (pinfunction "IP+_1") (pintype "bidirectional"))
    )
    (net (code "6") (name "12V-IMEAS") (class "Default")
      (node (ref "U$1") (pin "31") (pinfunction "D6~{/A7}_31") (pintype "bidirectional"))
      (node (ref "U$21") (pin "7") (pinfunction "VIOUT_7") (pintype "bidirectional"))
    )
    (net (code "7") (name "12V-SIG") (class "Default")
      (node (ref "R15") (pin "2") (pinfunction "2_2") (pintype "passive"))
      (node (ref "U$1") (pin "12") (pinfunction "PB0_12") (pintype "bidirectional"))
    )
    (net (code "8") (name "ARM_P-IMEAS") (class "Default")
      (node (ref "Q1") (pin "7") (pinfunction "VIOUT_7") (pintype "bidirectional"))
      (node (ref "U$1") (pin "20") (pinfunction "A4_20") (pintype "bidirectional"))
    )
    (net (code "9") (name "ARM_P-SIG") (class "Default")
      (node (ref "U$1") (pin "13") (pinfunction "D7_13") (pintype "bidirectional"))
      (node (ref "U$12") (pin "4") (pinfunction "IN_4") (pintype "bidirectional"))
    )
    (net (code "10") (name "AUX_P-IMEAS") (class "Default")
      (node (ref "U$1") (pin "30") (pinfunction "D8/A8_30") (pintype "bidirectional"))
      (node (ref "U$20") (pin "7") (pinfunction "VIOUT_7") (pintype "bidirectional"))
    )
    (net (code "11") (name "AUX_P-SIG") (class "Default")
      (node (ref "U$1") (pin "11") (pinfunction "SCK_11") (pintype "bidirectional"))
      (node (ref "U$13") (pin "4") (pinfunction "IN_4") (pintype "bidirectional"))
    )
    (net (code "12") (name "BUZZ_BUZZ_MOTHERFUCKER") (class "Default")
      (node (ref "Q2") (pin "1") (pinfunction "G_1") (pintype "passive"))
      (node (ref "U$1") (pin "8") (pinfunction "D11~{}_8") (pintype "bidirectional"))
    )
    (net (code "13") (name "CRIT-IMEAS") (class "Default")
      (node (ref "Q5") (pin "7") (pinfunction "VIOUT_7") (pintype "bidirectional"))
      (node (ref "U$1") (pin "1") (pinfunction "D4/A6_1") (pintype "bidirectional"))
    )
    (net (code "14") (name "GND") (class "Default")
      (node (ref "12V-AUX") (pin "L1") (pinfunction "L_L1") (pintype "bidirectional"))
      (node (ref "12V-AUX") (pin "L2") (pinfunction "L_L2") (pintype "bidirectional"))
      (node (ref "12V-CRIT") (pin "L") (pinfunction "L_L") (pintype "bidirectional"))
      (node (ref "5V-EXT") (pin "L") (pinfunction "L_L") (pintype "bidirectional"))
      (node (ref "5V-INT") (pin "L") (pinfunction "L_L") (pintype "bidirectional"))
      (node (ref "ARM_P") (pin "L") (pinfunction "L_L") (pintype "bidirectional"))
      (node (ref "AUX_P") (pin "L1") (pinfunction "L_L1") (pintype "bidirectional"))
      (node (ref "AUX_P") (pin "L2") (pinfunction "L_L2") (pintype "bidirectional"))
      (node (ref "BATT-NEG") (pin "P$1") (pinfunction "P$1_P$1") (pintype "bidirectional"))
      (node (ref "C1") (pin "-") (pinfunction "-_-") (pintype "passive"))
      (node (ref "C10") (pin "1") (pinfunction "1_1") (pintype "passive"))
      (node (ref "C11") (pin "2") (pinfunction "2_2") (pintype "passive"))
      (node (ref "C12") (pin "2") (pinfunction "2_2") (pintype "passive"))
      (node (ref "C13") (pin "1") (pinfunction "1_1") (pintype "passive"))
      (node (ref "C14") (pin "1") (pinfunction "1_1") (pintype "passive"))
      (node (ref "C15") (pin "1") (pinfunction "1_1") (pintype "passive"))
      (node (ref "C16") (pin "1") (pinfunction "1_1") (pintype "passive"))
      (node (ref "C17") (pin "2") (pinfunction "2_2") (pintype "passive"))
      (node (ref "C18") (pin "2") (pinfunction "2_2") (pintype "passive"))
      (node (ref "C19") (pin "2") (pinfunction "2_2") (pintype "passive"))
      (node (ref "C2") (pin "-") (pinfunction "-_-") (pintype "passive"))
      (node (ref "C20") (pin "2") (pinfunction "2_2") (pintype "passive"))
      (node (ref "C21") (pin "-") (pinfunction "-_-") (pintype "passive"))
      (node (ref "C22") (pin "-") (pinfunction "-_-") (pintype "passive"))
      (node (ref "C23") (pin "1") (pinfunction "1_1") (pintype "passive"))
      (node (ref "C24") (pin "1") (pinfunction "1_1") (pintype "passive"))
      (node (ref "C25") (pin "1") (pinfunction "1_1") (pintype "passive"))
      (node (ref "C26") (pin "1") (pinfunction "1_1") (pintype "passive"))
      (node (ref "C27") (pin "2") (pinfunction "2_2") (pintype "passive"))
      (node (ref "C28") (pin "1") (pinfunction "1_1") (pintype "passive"))
      (node (ref "C29") (pin "1") (pinfunction "1_1") (pintype "passive"))
      (node (ref "C3") (pin "-") (pinfunction "-_-") (pintype "passive"))
      (node (ref "C30") (pin "1") (pinfunction "1_1") (pintype "passive"))
      (node (ref "C31") (pin "2") (pinfunction "2_2") (pintype "passive"))
      (node (ref "C32") (pin "1") (pinfunction "1_1") (pintype "passive"))
      (node (ref "C33") (pin "1") (pinfunction "1_1") (pintype "passive"))
      (node (ref "C34") (pin "1") (pinfunction "1_1") (pintype "passive"))
      (node (ref "C35") (pin "2") (pinfunction "2_2") (pintype "passive"))
      (node (ref "C36") (pin "1") (pinfunction "1_1") (pintype "passive"))
      (node (ref "C37") (pin "2") (pinfunction "2_2") (pintype "passive"))
      (node (ref "C38") (pin "2") (pinfunction "2_2") (pintype "passive"))
      (node (ref "C39") (pin "1") (pinfunction "1_1") (pintype "passive"))
      (node (ref "C4") (pin "-") (pinfunction "-_-") (pintype "passive"))
      (node (ref "C40") (pin "2") (pinfunction "2_2") (pintype "passive"))
      (node (ref "C41") (pin "1") (pinfunction "1_1") (pintype "passive"))
      (node (ref "C42") (pin "2") (pinfunction "2_2") (pintype "passive"))
      (node (ref "C43") (pin "2") (pinfunction "2_2") (pintype "passive"))
      (node (ref "C44") (pin "2") (pinfunction "2_2") (pintype "passive"))
      (node (ref "C45") (pin "-") (pinfunction "-_-") (pintype "passive"))
      (node (ref "C46") (pin "-") (pinfunction "-_-") (pintype "passive"))
      (node (ref "C47") (pin "2") (pinfunction "2_2") (pintype "passive"))
      (node (ref "C48") (pin "2") (pinfunction "2_2") (pintype "passive"))
      (node (ref "C49") (pin "2") (pinfunction "2_2") (pintype "passive"))
      (node (ref "C5") (pin "1") (pinfunction "1_1") (pintype "passive"))
      (node (ref "C50") (pin "2") (pinfunction "2_2") (pintype "passive"))
      (node (ref "C51") (pin "2") (pinfunction "2_2") (pintype "passive"))
      (node (ref "C52") (pin "2") (pinfunction "2_2") (pintype "passive"))
      (node (ref "C6") (pin "1") (pinfunction "1_1") (pintype "passive"))
      (node (ref "C7") (pin "2") (pinfunction "2_2") (pintype "passive"))
      (node (ref "C8") (pin "2") (pinfunction "2_2") (pintype "passive"))
      (node (ref "C9") (pin "2") (pinfunction "2_2") (pintype "passive"))
      (node (ref "D1") (pin "A") (pinfunction "A_A") (pintype "passive"))
      (node (ref "D2") (pin "A") (pinfunction "A_A") (pintype "passive"))
      (node (ref "DOOKU-12V-CRIT") (pin "1") (pinfunction "GND_1") (pintype "bidirectional"))
      (node (ref "DOOKU-12V-CRIT") (pin "7") (pinfunction "GND1_7") (pintype "bidirectional"))
      (node (ref "JP1") (pin "2") (pinfunction "2_2") (pintype "passive"))
      (node (ref "LED1") (pin "C") (pinfunction "C_C") (pintype "passive"))
      (node (ref "LED10") (pin "C") (pinfunction "C_C") (pintype "passive"))
      (node (ref "LED11") (pin "C") (pinfunction "C_C") (pintype "passive"))
      (node (ref "LED12") (pin "C") (pinfunction "C_C") (pintype "passive"))
      (node (ref "LED13") (pin "C") (pinfunction "C_C") (pintype "passive"))
      (node (ref "LED2") (pin "C") (pinfunction "C_C") (pintype "passive"))
      (node (ref "LED6") (pin "C") (pinfunction "C_C") (pintype "passive"))
      (node (ref "LED7") (pin "C") (pinfunction "C_C") (pintype "passive"))
      (node (ref "LED8") (pin "C") (pinfunction "C_C") (pintype "passive"))
      (node (ref "LED9") (pin "C") (pinfunction "C_C") (pintype "passive"))
      (node (ref "MOTOR_1") (pin "L1") (pinfunction "L_L1") (pintype "bidirectional"))
      (node (ref "MOTOR_1") (pin "L2") (pinfunction "L_L2") (pintype "bidirectional"))
      (node (ref "MOTOR_2") (pin "L1") (pinfunction "L_L1") (pintype "bidirectional"))
      (node (ref "MOTOR_2") (pin "L2") (pinfunction "L_L2") (pintype "bidirectional"))
      (node (ref "MOTOR_3") (pin "L1") (pinfunction "L_L1") (pintype "bidirectional"))
      (node (ref "MOTOR_3") (pin "L2") (pinfunction "L_L2") (pintype "bidirectional"))
      (node (ref "MOTOR_4") (pin "L1") (pinfunction "L_L1") (pintype "bidirectional"))
      (node (ref "MOTOR_4") (pin "L2") (pinfunction "L_L2") (pintype "bidirectional"))
      (node (ref "MOTOR_5") (pin "L1") (pinfunction "L_L1") (pintype "bidirectional"))
      (node (ref "MOTOR_5") (pin "L2") (pinfunction "L_L2") (pintype "bidirectional"))
      (node (ref "MOTOR_6") (pin "L1") (pinfunction "L_L1") (pintype "bidirectional"))
      (node (ref "MOTOR_6") (pin "L2") (pinfunction "L_L2") (pintype "bidirectional"))
      (node (ref "OKI-78SR-5/1.5-W36H") (pin "2") (pinfunction "GND_2") (pintype "bidirectional"))
      (node (ref "PALPATINE-12V") (pin "3") (pinfunction "-VIN_3") (pintype "bidirectional"))
      (node (ref "PALPATINE-12V") (pin "4") (pinfunction "-VOUT_4") (pintype "bidirectional"))
      (node (ref "Q1") (pin "5") (pinfunction "GND_5") (pintype "bidirectional"))
      (node (ref "Q12") (pin "2") (pinfunction "S_2") (pintype "passive"))
      (node (ref "Q2") (pin "2") (pinfunction "S_2") (pintype "passive"))
      (node (ref "Q4") (pin "5") (pinfunction "GND_5") (pintype "bidirectional"))
      (node (ref "Q5") (pin "5") (pinfunction "GND_5") (pintype "bidirectional"))
      (node (ref "R11") (pin "2") (pinfunction "2_2") (pintype "passive"))
      (node (ref "R12") (pin "2") (pinfunction "2_2") (pintype "passive"))
      (node (ref "R13") (pin "2") (pinfunction "2_2") (pintype "passive"))
      (node (ref "R4") (pin "1") (pinfunction "1_1") (pintype "passive"))
      (node (ref "R7") (pin "1") (pinfunction "1_1") (pintype "passive"))
      (node (ref "R8") (pin "1") (pinfunction "1_1") (pintype "passive"))
      (node (ref "SIDEOUS-12V") (pin "3") (pinfunction "-VIN_3") (pintype "bidirectional"))
      (node (ref "SIDEOUS-12V") (pin "4") (pinfunction "-VOUT_4") (pintype "bidirectional"))
      (node (ref "U$1") (pin "15") (pinfunction "GND_15") (pintype "bidirectional"))
      (node (ref "U$1") (pin "17") (pinfunction "GND_17") (pintype "bidirectional"))
      (node (ref "U$10") (pin "1") (pinfunction "GND_1") (pintype "bidirectional"))
      (node (ref "U$11") (pin "1") (pinfunction "GND_1") (pintype "bidirectional"))
      (node (ref "U$12") (pin "1") (pinfunction "GND_1") (pintype "bidirectional"))
      (node (ref "U$13") (pin "1") (pinfunction "GND_1") (pintype "bidirectional"))
      (node (ref "U$14") (pin "5") (pinfunction "GND_5") (pintype "bidirectional"))
      (node (ref "U$15") (pin "5") (pinfunction "GND_5") (pintype "bidirectional"))
      (node (ref "U$16") (pin "5") (pinfunction "GND_5") (pintype "bidirectional"))
      (node (ref "U$17") (pin "5") (pinfunction "GND_5") (pintype "bidirectional"))
      (node (ref "U$18") (pin "5") (pinfunction "GND_5") (pintype "bidirectional"))
      (node (ref "U$19") (pin "5") (pinfunction "GND_5") (pintype "bidirectional"))
      (node (ref "U$2") (pin "2") (pinfunction "A_2") (pintype "passive"))
      (node (ref "U$20") (pin "5") (pinfunction "GND_5") (pintype "bidirectional"))
      (node (ref "U$21") (pin "5") (pinfunction "GND_5") (pintype "bidirectional"))
      (node (ref "U$3") (pin "GND") (pinfunction "GND_GND") (pintype "bidirectional"))
      (node (ref "U$4") (pin "7") (pinfunction "7_7") (pintype "bidirectional"))
      (node (ref "U$4") (pin "8") (pinfunction "8_8") (pintype "bidirectional"))
      (node (ref "U$5") (pin "2") (pinfunction "A_2") (pintype "passive"))
      (node (ref "U$6") (pin "1") (pinfunction "GND_1") (pintype "bidirectional"))
      (node (ref "U$7") (pin "1") (pinfunction "GND_1") (pintype "bidirectional"))
      (node (ref "U$8") (pin "1") (pinfunction "GND_1") (pintype "bidirectional"))
      (node (ref "U$9") (pin "1") (pinfunction "GND_1") (pintype "bidirectional"))
      (node (ref "VADER-5V-EXT") (pin "1") (pinfunction "GND_1") (pintype "bidirectional"))
      (node (ref "VADER-5V-EXT") (pin "7") (pinfunction "GND1_7") (pintype "bidirectional"))
    )
    (net (code "15") (name "INFO_LED") (class "Default")
      (node (ref "R1") (pin "1") (pinfunction "1_1") (pintype "passive"))
      (node (ref "U$1") (pin "9") (pinfunction "MISO_9") (pintype "bidirectional"))
    )
    (net (code "16") (name "JUMPER_SIG_IN") (class "Default")
      (node (ref "JP1") (pin "1") (pinfunction "1_1") (pintype "passive"))
      (node (ref "R2") (pin "1") (pinfunction "1_1") (pintype "passive"))
      (node (ref "U$1") (pin "10") (pinfunction "MOSI_10") (pintype "bidirectional"))
    )
    (net (code "17") (name "M1-IMEAS") (class "Default")
      (node (ref "U$1") (pin "21") (pinfunction "A3_21") (pintype "bidirectional"))
      (node (ref "U$14") (pin "7") (pinfunction "VIOUT_7") (pintype "bidirectional"))
    )
    (net (code "18") (name "M1-SIG") (class "Default")
      (node (ref "U$1") (pin "25") (pinfunction "PE2_25") (pintype "bidirectional"))
      (node (ref "U$6") (pin "4") (pinfunction "IN_4") (pintype "bidirectional"))
    )
    (net (code "19") (name "M2-IMEAS") (class "Default")
      (node (ref "U$1") (pin "22") (pinfunction "A2_22") (pintype "bidirectional"))
      (node (ref "U$15") (pin "7") (pinfunction "VIOUT_7") (pintype "bidirectional"))
    )
    (net (code "20") (name "M2-SIG") (class "Default")
      (node (ref "U$1") (pin "26") (pinfunction "D13~{}_26") (pintype "bidirectional"))
      (node (ref "U$7") (pin "4") (pinfunction "IN_4") (pintype "bidirectional"))
    )
    (net (code "21") (name "M3-IMEAS") (class "Default")
      (node (ref "U$1") (pin "23") (pinfunction "A1_23") (pintype "bidirectional"))
      (node (ref "U$19") (pin "7") (pinfunction "VIOUT_7") (pintype "bidirectional"))
    )
    (net (code "22") (name "M3-SIG") (class "Default")
      (node (ref "U$1") (pin "27") (pinfunction "D5~{}_27") (pintype "bidirectional"))
      (node (ref "U$8") (pin "4") (pinfunction "IN_4") (pintype "bidirectional"))
    )
    (net (code "23") (name "M4-IMEAS") (class "Default")
      (node (ref "U$1") (pin "24") (pinfunction "A0_24") (pintype "bidirectional"))
      (node (ref "U$18") (pin "7") (pinfunction "VIOUT_7") (pintype "bidirectional"))
    )
    (net (code "24") (name "M4-SIG") (class "Default")
      (node (ref "U$1") (pin "2") (pinfunction "PD5_2") (pintype "bidirectional"))
      (node (ref "U$9") (pin "4") (pinfunction "IN_4") (pintype "bidirectional"))
    )
    (net (code "25") (name "M5-IMEAS") (class "Default")
      (node (ref "U$1") (pin "28") (pinfunction "D10~{/A10}_28") (pintype "bidirectional"))
      (node (ref "U$17") (pin "7") (pinfunction "VIOUT_7") (pintype "bidirectional"))
    )
    (net (code "26") (name "M5-SIG") (class "Default")
      (node (ref "U$1") (pin "5") (pinfunction "D2_5") (pintype "bidirectional"))
      (node (ref "U$10") (pin "4") (pinfunction "IN_4") (pintype "bidirectional"))
    )
    (net (code "27") (name "M6-IMEAS") (class "Default")
      (node (ref "U$1") (pin "29") (pinfunction "D9~{/A9}_29") (pintype "bidirectional"))
      (node (ref "U$16") (pin "7") (pinfunction "VIOUT_7") (pintype "bidirectional"))
    )
    (net (code "28") (name "M6-SIG") (class "Default")
      (node (ref "U$1") (pin "6") (pinfunction "D3~{}_6") (pintype "bidirectional"))
      (node (ref "U$11") (pin "4") (pinfunction "IN_4") (pintype "bidirectional"))
    )
    (net (code "29") (name "Net-(DOOKU-12V-CRIT-ADJUST)") (class "Default")
      (node (ref "DOOKU-12V-CRIT") (pin "4") (pinfunction "ADJUST_4") (pintype "bidirectional"))
      (node (ref "R7") (pin "2") (pinfunction "2_2") (pintype "passive"))
    )
    (net (code "30") (name "Net-(DOOKU-12V-CRIT-SENSE)") (class "Default")
      (node (ref "C21") (pin "+") (pinfunction "+_+") (pintype "passive"))
      (node (ref "C9") (pin "1") (pinfunction "1_1") (pintype "passive"))
      (node (ref "DOOKU-12V-CRIT") (pin "5") (pinfunction "SENSE_5") (pintype "bidirectional"))
      (node (ref "DOOKU-12V-CRIT") (pin "6") (pinfunction "VOUT_6") (pintype "bidirectional"))
      (node (ref "Q5") (pin "4") (pinfunction "IP-_4") (pintype "bidirectional"))
      (node (ref "U$5") (pin "1") (pinfunction "C_1") (pintype "passive"))
    )
    (net (code "31") (name "Net-(LED1-PadA)") (class "Default")
      (node (ref "LED1") (pin "A") (pinfunction "A_A") (pintype "passive"))
      (node (ref "R9") (pin "2") (pinfunction "2_2") (pintype "passive"))
    )
    (net (code "32") (name "Net-(LED2-PadA)") (class "Default")
      (node (ref "LED2") (pin "A") (pinfunction "A_A") (pintype "passive"))
      (node (ref "R10") (pin "2") (pinfunction "2_2") (pintype "passive"))
    )
    (net (code "33") (name "Net-(LED3-PadC)") (class "Default")
      (node (ref "LED3") (pin "C") (pinfunction "C_C") (pintype "passive"))
      (node (ref "R11") (pin "1") (pinfunction "1_1") (pintype "passive"))
    )
    (net (code "34") (name "Net-(LED4-PadC)") (class "Default")
      (node (ref "LED4") (pin "C") (pinfunction "C_C") (pintype "passive"))
      (node (ref "R12") (pin "1") (pinfunction "1_1") (pintype "passive"))
    )
    (net (code "35") (name "Net-(LED5-PadC)") (class "Default")
      (node (ref "LED5") (pin "C") (pinfunction "C_C") (pintype "passive"))
      (node (ref "R13") (pin "1") (pinfunction "1_1") (pintype "passive"))
    )
    (net (code "36") (name "Net-(LED6-PadA)") (class "Default")
      (node (ref "LED6") (pin "A") (pinfunction "A_A") (pintype "passive"))
      (node (ref "R16") (pin "2") (pinfunction "2_2") (pintype "passive"))
    )
    (net (code "37") (name "Net-(LED7-PadA)") (class "Default")
      (node (ref "LED7") (pin "A") (pinfunction "A_A") (pintype "passive"))
      (node (ref "R18") (pin "2") (pinfunction "2_2") (pintype "passive"))
    )
    (net (code "38") (name "Net-(LED8-PadA)") (class "Default")
      (node (ref "LED8") (pin "A") (pinfunction "A_A") (pintype "passive"))
      (node (ref "R20") (pin "2") (pinfunction "2_2") (pintype "passive"))
    )
    (net (code "39") (name "Net-(LED9-PadA)") (class "Default")
      (node (ref "LED9") (pin "A") (pinfunction "A_A") (pintype "passive"))
      (node (ref "R22") (pin "2") (pinfunction "2_2") (pintype "passive"))
    )
    (net (code "40") (name "Net-(LED10-PadA)") (class "Default")
      (node (ref "LED10") (pin "A") (pinfunction "A_A") (pintype "passive"))
      (node (ref "R24") (pin "2") (pinfunction "2_2") (pintype "passive"))
    )
    (net (code "41") (name "Net-(LED11-PadA)") (class "Default")
      (node (ref "LED11") (pin "A") (pinfunction "A_A") (pintype "passive"))
      (node (ref "R26") (pin "2") (pinfunction "2_2") (pintype "passive"))
    )
    (net (code "42") (name "Net-(LED12-PadA)") (class "Default")
      (node (ref "LED12") (pin "A") (pinfunction "A_A") (pintype "passive"))
      (node (ref "R28") (pin "2") (pinfunction "2_2") (pintype "passive"))
    )
    (net (code "43") (name "Net-(LED13-PadA)") (class "Default")
      (node (ref "LED13") (pin "A") (pinfunction "A_A") (pintype "passive"))
      (node (ref "R1") (pin "2") (pinfunction "2_2") (pintype "passive"))
    )
    (net (code "44") (name "Net-(OKI-78SR-5/1.5-W36H-VO)") (class "Default")
      (node (ref "C17") (pin "1") (pinfunction "1_1") (pintype "passive"))
      (node (ref "L3") (pin "1") (pinfunction "1_1") (pintype "passive"))
      (node (ref "OKI-78SR-5/1.5-W36H") (pin "3") (pinfunction "VO_3") (pintype "bidirectional"))
    )
    (net (code "45") (name "Net-(PALPATINE-12V-+VOUT)") (class "Default")
      (node (ref "C19") (pin "1") (pinfunction "1_1") (pintype "passive"))
      (node (ref "C20") (pin "1") (pinfunction "1_1") (pintype "passive"))
      (node (ref "C45") (pin "+") (pinfunction "+_+") (pintype "passive"))
      (node (ref "C46") (pin "+") (pinfunction "+_+") (pintype "passive"))
      (node (ref "PALPATINE-12V") (pin "8") (pinfunction "+VOUT_8") (pintype "bidirectional"))
      (node (ref "SIDEOUS-12V") (pin "8") (pinfunction "+VOUT_8") (pintype "bidirectional"))
      (node (ref "U$21") (pin "1") (pinfunction "IP+_1") (pintype "bidirectional"))
    )
    (net (code "46") (name "Net-(PALPATINE-12V-REMOTE)") (class "Default")
      (node (ref "PALPATINE-12V") (pin "2") (pinfunction "REMOTE_2") (pintype "bidirectional"))
      (node (ref "Q12") (pin "3") (pinfunction "D_3") (pintype "passive"))
      (node (ref "SIDEOUS-12V") (pin "2") (pinfunction "REMOTE_2") (pintype "bidirectional"))
    )
    (net (code "47") (name "Net-(Q1-IP-)") (class "Default")
      (node (ref "C34") (pin "2") (pinfunction "2_2") (pintype "passive"))
      (node (ref "Q1") (pin "4") (pinfunction "IP-_4") (pintype "bidirectional"))
      (node (ref "Q18") (pin "2") (pinfunction "D_2") (pintype "bidirectional"))
      (node (ref "Q18") (pin "4") (pinfunction "D_4") (pintype "bidirectional"))
      (node (ref "U$12") (pin "6") (pinfunction "SENSE_6") (pintype "bidirectional"))
      (node (ref "U$12") (pin "8") (pinfunction "V+_8") (pintype "bidirectional"))
    )
    (net (code "48") (name "Net-(Q2-D)") (class "Default")
      (node (ref "Q2") (pin "3") (pinfunction "D_3") (pintype "passive"))
      (node (ref "SG1") (pin "-") (pinfunction "2_-") (pintype "passive"))
    )
    (net (code "49") (name "Net-(Q4-IP+)") (class "Default")
      (node (ref "C11") (pin "1") (pinfunction "1_1") (pintype "passive"))
      (node (ref "C22") (pin "+") (pinfunction "+_+") (pintype "passive"))
      (node (ref "Q4") (pin "1") (pinfunction "IP+_1") (pintype "bidirectional"))
      (node (ref "U$2") (pin "1") (pinfunction "C_1") (pintype "passive"))
      (node (ref "VADER-5V-EXT") (pin "5") (pinfunction "SENSE_5") (pintype "bidirectional"))
      (node (ref "VADER-5V-EXT") (pin "6") (pinfunction "VOUT_6") (pintype "bidirectional"))
    )
    (net (code "50") (name "Net-(Q6-D)") (class "Default")
      (node (ref "C16") (pin "2") (pinfunction "2_2") (pintype "passive"))
      (node (ref "Q6") (pin "TAB") (pinfunction "D_TAB") (pintype "bidirectional"))
      (node (ref "U$14") (pin "4") (pinfunction "IP-_4") (pintype "bidirectional"))
      (node (ref "U$6") (pin "6") (pinfunction "SENSE_6") (pintype "bidirectional"))
      (node (ref "U$6") (pin "8") (pinfunction "V+_8") (pintype "bidirectional"))
    )
    (net (code "51") (name "Net-(Q6-G)") (class "Default")
      (node (ref "Q6") (pin "1") (pinfunction "G_1") (pintype "bidirectional"))
      (node (ref "U$6") (pin "5") (pinfunction "GATE_5") (pintype "bidirectional"))
    )
    (net (code "52") (name "Net-(Q6-S)") (class "Default")
      (node (ref "MOTOR_1") (pin "R1") (pinfunction "R_R1") (pintype "bidirectional"))
      (node (ref "MOTOR_1") (pin "R2") (pinfunction "R_R2") (pintype "bidirectional"))
      (node (ref "Q6") (pin "2") (pinfunction "S_2") (pintype "bidirectional"))
      (node (ref "R9") (pin "1") (pinfunction "1_1") (pintype "passive"))
    )
    (net (code "53") (name "Net-(Q7-D)") (class "Default")
      (node (ref "C24") (pin "2") (pinfunction "2_2") (pintype "passive"))
      (node (ref "Q7") (pin "TAB") (pinfunction "D_TAB") (pintype "bidirectional"))
      (node (ref "U$15") (pin "4") (pinfunction "IP-_4") (pintype "bidirectional"))
      (node (ref "U$7") (pin "6") (pinfunction "SENSE_6") (pintype "bidirectional"))
      (node (ref "U$7") (pin "8") (pinfunction "V+_8") (pintype "bidirectional"))
    )
    (net (code "54") (name "Net-(Q7-G)") (class "Default")
      (node (ref "Q7") (pin "1") (pinfunction "G_1") (pintype "bidirectional"))
      (node (ref "U$7") (pin "5") (pinfunction "GATE_5") (pintype "bidirectional"))
    )
    (net (code "55") (name "Net-(Q7-S)") (class "Default")
      (node (ref "MOTOR_2") (pin "R1") (pinfunction "R_R1") (pintype "bidirectional"))
      (node (ref "MOTOR_2") (pin "R2") (pinfunction "R_R2") (pintype "bidirectional"))
      (node (ref "Q7") (pin "2") (pinfunction "S_2") (pintype "bidirectional"))
      (node (ref "R16") (pin "1") (pinfunction "1_1") (pintype "passive"))
    )
    (net (code "56") (name "Net-(Q9-D)") (class "Default")
      (node (ref "C26") (pin "2") (pinfunction "2_2") (pintype "passive"))
      (node (ref "Q9") (pin "TAB") (pinfunction "D_TAB") (pintype "bidirectional"))
      (node (ref "U$19") (pin "4") (pinfunction "IP-_4") (pintype "bidirectional"))
      (node (ref "U$8") (pin "6") (pinfunction "SENSE_6") (pintype "bidirectional"))
      (node (ref "U$8") (pin "8") (pinfunction "V+_8") (pintype "bidirectional"))
    )
    (net (code "57") (name "Net-(Q9-G)") (class "Default")
      (node (ref "Q9") (pin "1") (pinfunction "G_1") (pintype "bidirectional"))
      (node (ref "U$8") (pin "5") (pinfunction "GATE_5") (pintype "bidirectional"))
    )
    (net (code "58") (name "Net-(Q9-S)") (class "Default")
      (node (ref "MOTOR_3") (pin "R1") (pinfunction "R_R1") (pintype "bidirectional"))
      (node (ref "MOTOR_3") (pin "R2") (pinfunction "R_R2") (pintype "bidirectional"))
      (node (ref "Q9") (pin "2") (pinfunction "S_2") (pintype "bidirectional"))
      (node (ref "R18") (pin "1") (pinfunction "1_1") (pintype "passive"))
    )
    (net (code "59") (name "Net-(Q11-D)") (class "Default")
      (node (ref "C28") (pin "2") (pinfunction "2_2") (pintype "passive"))
      (node (ref "Q11") (pin "TAB") (pinfunction "D_TAB") (pintype "bidirectional"))
      (node (ref "U$18") (pin "4") (pinfunction "IP-_4") (pintype "bidirectional"))
      (node (ref "U$9") (pin "6") (pinfunction "SENSE_6") (pintype "bidirectional"))
      (node (ref "U$9") (pin "8") (pinfunction "V+_8") (pintype "bidirectional"))
    )
    (net (code "60") (name "Net-(Q11-G)") (class "Default")
      (node (ref "Q11") (pin "1") (pinfunction "G_1") (pintype "bidirectional"))
      (node (ref "U$9") (pin "5") (pinfunction "GATE_5") (pintype "bidirectional"))
    )
    (net (code "61") (name "Net-(Q11-S)") (class "Default")
      (node (ref "MOTOR_4") (pin "R1") (pinfunction "R_R1") (pintype "bidirectional"))
      (node (ref "MOTOR_4") (pin "R2") (pinfunction "R_R2") (pintype "bidirectional"))
      (node (ref "Q11") (pin "2") (pinfunction "S_2") (pintype "bidirectional"))
      (node (ref "R20") (pin "1") (pinfunction "1_1") (pintype "passive"))
    )
    (net (code "62") (name "Net-(Q12-G)") (class "Default")
      (node (ref "Q12") (pin "1") (pinfunction "G_1") (pintype "passive"))
      (node (ref "R15") (pin "1") (pinfunction "1_1") (pintype "passive"))
    )
    (net (code "63") (name "Net-(Q14-D)") (class "Default")
      (node (ref "C30") (pin "2") (pinfunction "2_2") (pintype "passive"))
      (node (ref "Q14") (pin "TAB") (pinfunction "D_TAB") (pintype "bidirectional"))
      (node (ref "U$10") (pin "6") (pinfunction "SENSE_6") (pintype "bidirectional"))
      (node (ref "U$10") (pin "8") (pinfunction "V+_8") (pintype "bidirectional"))
      (node (ref "U$17") (pin "4") (pinfunction "IP-_4") (pintype "bidirectional"))
    )
    (net (code "64") (name "Net-(Q14-G)") (class "Default")
      (node (ref "Q14") (pin "1") (pinfunction "G_1") (pintype "bidirectional"))
      (node (ref "U$10") (pin "5") (pinfunction "GATE_5") (pintype "bidirectional"))
    )
    (net (code "65") (name "Net-(Q14-S)") (class "Default")
      (node (ref "MOTOR_5") (pin "R1") (pinfunction "R_R1") (pintype "bidirectional"))
      (node (ref "MOTOR_5") (pin "R2") (pinfunction "R_R2") (pintype "bidirectional"))
      (node (ref "Q14") (pin "2") (pinfunction "S_2") (pintype "bidirectional"))
      (node (ref "R22") (pin "1") (pinfunction "1_1") (pintype "passive"))
    )
    (net (code "66") (name "Net-(Q16-D)") (class "Default")
      (node (ref "C32") (pin "2") (pinfunction "2_2") (pintype "passive"))
      (node (ref "Q16") (pin "TAB") (pinfunction "D_TAB") (pintype "bidirectional"))
      (node (ref "U$11") (pin "6") (pinfunction "SENSE_6") (pintype "bidirectional"))
      (node (ref "U$11") (pin "8") (pinfunction "V+_8") (pintype "bidirectional"))
      (node (ref "U$16") (pin "4") (pinfunction "IP-_4") (pintype "bidirectional"))
    )
    (net (code "67") (name "Net-(Q16-G)") (class "Default")
      (node (ref "Q16") (pin "1") (pinfunction "G_1") (pintype "bidirectional"))
      (node (ref "U$11") (pin "5") (pinfunction "GATE_5") (pintype "bidirectional"))
    )
    (net (code "68") (name "Net-(Q16-S)") (class "Default")
      (node (ref "MOTOR_6") (pin "R1") (pinfunction "R_R1") (pintype "bidirectional"))
      (node (ref "MOTOR_6") (pin "R2") (pinfunction "R_R2") (pintype "bidirectional"))
      (node (ref "Q16") (pin "2") (pinfunction "S_2") (pintype "bidirectional"))
      (node (ref "R24") (pin "1") (pinfunction "1_1") (pintype "passive"))
    )
    (net (code "69") (name "Net-(Q18-G)") (class "Default")
      (node (ref "Q18") (pin "1") (pinfunction "G_1") (pintype "bidirectional"))
      (node (ref "U$12") (pin "5") (pinfunction "GATE_5") (pintype "bidirectional"))
    )
    (net (code "70") (name "Net-(Q18-S)") (class "Default")
      (node (ref "ARM_P") (pin "R") (pinfunction "R_R") (pintype "bidirectional"))
      (node (ref "Q18") (pin "3") (pinfunction "S_3") (pintype "bidirectional"))
      (node (ref "R26") (pin "1") (pinfunction "1_1") (pintype "passive"))
    )
    (net (code "71") (name "Net-(Q20-D)") (class "Default")
      (node (ref "C36") (pin "2") (pinfunction "2_2") (pintype "passive"))
      (node (ref "Q20") (pin "TAB") (pinfunction "D_TAB") (pintype "bidirectional"))
      (node (ref "U$13") (pin "6") (pinfunction "SENSE_6") (pintype "bidirectional"))
      (node (ref "U$13") (pin "8") (pinfunction "V+_8") (pintype "bidirectional"))
      (node (ref "U$20") (pin "4") (pinfunction "IP-_4") (pintype "bidirectional"))
    )
    (net (code "72") (name "Net-(Q20-G)") (class "Default")
      (node (ref "Q20") (pin "1") (pinfunction "G_1") (pintype "bidirectional"))
      (node (ref "U$13") (pin "5") (pinfunction "GATE_5") (pintype "bidirectional"))
    )
    (net (code "73") (name "Net-(Q20-S)") (class "Default")
      (node (ref "AUX_P") (pin "R1") (pinfunction "R_R1") (pintype "bidirectional"))
      (node (ref "AUX_P") (pin "R2") (pinfunction "R_R2") (pintype "bidirectional"))
      (node (ref "Q20") (pin "2") (pinfunction "S_2") (pintype "bidirectional"))
      (node (ref "R28") (pin "1") (pinfunction "1_1") (pintype "passive"))
    )
    (net (code "74") (name "Net-(R5-Pad1)") (class "Default")
      (node (ref "R5") (pin "1") (pinfunction "1_1") (pintype "passive"))
      (node (ref "U$3") (pin "A") (pinfunction "A_A") (pintype "bidirectional"))
      (node (ref "U$4") (pin "3") (pinfunction "3_3") (pintype "bidirectional"))
    )
    (net (code "75") (name "Net-(R5-Pad2)") (class "Default")
      (node (ref "R5") (pin "2") (pinfunction "2_2") (pintype "passive"))
      (node (ref "U$3") (pin "B") (pinfunction "B_B") (pintype "bidirectional"))
      (node (ref "U$4") (pin "6") (pinfunction "6_6") (pintype "bidirectional"))
    )
    (net (code "76") (name "Net-(R6-Pad1)") (class "Default")
      (node (ref "R6") (pin "1") (pinfunction "1_1") (pintype "passive"))
      (node (ref "U$3") (pin "Z") (pinfunction "Z_Z") (pintype "bidirectional"))
      (node (ref "U$4") (pin "2") (pinfunction "2_2") (pintype "bidirectional"))
    )
    (net (code "77") (name "Net-(R6-Pad2)") (class "Default")
      (node (ref "R6") (pin "2") (pinfunction "2_2") (pintype "passive"))
      (node (ref "U$3") (pin "Y") (pinfunction "Y_Y") (pintype "bidirectional"))
      (node (ref "U$4") (pin "1") (pinfunction "1_1") (pintype "bidirectional"))
    )
    (net (code "78") (name "Net-(U$1-D0{slash}RX)") (class "Default")
      (node (ref "U$1") (pin "4") (pinfunction "D0/RX_4") (pintype "bidirectional"))
      (node (ref "U$3") (pin "RO") (pinfunction "R0_RO") (pintype "bidirectional"))
    )
    (net (code "79") (name "Net-(U$1-D1{slash}TX)") (class "Default")
      (node (ref "U$1") (pin "3") (pinfunction "D1/TX_3") (pintype "bidirectional"))
      (node (ref "U$3") (pin "DI") (pinfunction "DI_DI") (pintype "bidirectional"))
    )
    (net (code "80") (name "Net-(U$14-FILTER)") (class "Default")
      (node (ref "C37") (pin "1") (pinfunction "1_1") (pintype "passive"))
      (node (ref "U$14") (pin "6") (pinfunction "FILTER_6") (pintype "bidirectional"))
    )
    (net (code "81") (name "Net-(U$15-FILTER)") (class "Default")
      (node (ref "C38") (pin "1") (pinfunction "1_1") (pintype "passive"))
      (node (ref "U$15") (pin "6") (pinfunction "FILTER_6") (pintype "bidirectional"))
    )
    (net (code "82") (name "Net-(U$16-FILTER)") (class "Default")
      (node (ref "C27") (pin "1") (pinfunction "1_1") (pintype "passive"))
      (node (ref "U$16") (pin "6") (pinfunction "FILTER_6") (pintype "bidirectional"))
    )
    (net (code "83") (name "Net-(U$17-FILTER)") (class "Default")
      (node (ref "C31") (pin "1") (pinfunction "1_1") (pintype "passive"))
      (node (ref "U$17") (pin "6") (pinfunction "FILTER_6") (pintype "bidirectional"))
    )
    (net (code "84") (name "Net-(U$18-FILTER)") (class "Default")
      (node (ref "C35") (pin "1") (pinfunction "1_1") (pintype "passive"))
      (node (ref "U$18") (pin "6") (pinfunction "FILTER_6") (pintype "bidirectional"))
    )
    (net (code "85") (name "Net-(U$19-FILTER)") (class "Default")
      (node (ref "C40") (pin "1") (pinfunction "1_1") (pintype "passive"))
      (node (ref "U$19") (pin "6") (pinfunction "FILTER_6") (pintype "bidirectional"))
    )
    (net (code "86") (name "Net-(U$20-FILTER)") (class "Default")
      (node (ref "C42") (pin "1") (pinfunction "1_1") (pintype "passive"))
      (node (ref "U$20") (pin "6") (pinfunction "FILTER_6") (pintype "bidirectional"))
    )
    (net (code "87") (name "Net-(U$21-FILTER)") (class "Default")
      (node (ref "C43") (pin "1") (pinfunction "1_1") (pintype "passive"))
      (node (ref "U$21") (pin "6") (pinfunction "FILTER_6") (pintype "bidirectional"))
    )
    (net (code "88") (name "Net-(VADER-5V-EXT-ADJUST)") (class "Default")
      (node (ref "R8") (pin "2") (pinfunction "2_2") (pintype "passive"))
      (node (ref "VADER-5V-EXT") (pin "4") (pinfunction "ADJUST_4") (pintype "bidirectional"))
    )
    (net (code "89") (name "PRIMARY-VMEAS") (class "Default")
      (node (ref "R3") (pin "1") (pinfunction "1_1") (pintype "passive"))
      (node (ref "R4") (pin "2") (pinfunction "2_2") (pintype "passive"))
      (node (ref "U$1") (pin "19") (pinfunction "A5_19") (pintype "bidirectional"))
    )
    (net (code "90") (name "V_BATT") (class "Default")
      (node (ref "BATT-POS") (pin "P$1") (pinfunction "P$1_P$1") (pintype "bidirectional"))
      (node (ref "C1") (pin "+") (pinfunction "+_+") (pintype "passive"))
      (node (ref "C10") (pin "2") (pinfunction "2_2") (pintype "passive"))
      (node (ref "C13") (pin "2") (pinfunction "2_2") (pintype "passive"))
      (node (ref "C14") (pin "2") (pinfunction "2_2") (pintype "passive"))
      (node (ref "C15") (pin "2") (pinfunction "2_2") (pintype "passive"))
      (node (ref "C2") (pin "+") (pinfunction "+_+") (pintype "passive"))
      (node (ref "C3") (pin "+") (pinfunction "+_+") (pintype "passive"))
      (node (ref "C4") (pin "+") (pinfunction "+_+") (pintype "passive"))
      (node (ref "D1") (pin "C") (pinfunction "C_C") (pintype "passive"))
      (node (ref "D2") (pin "C") (pinfunction "C_C") (pintype "passive"))
      (node (ref "DOOKU-12V-CRIT") (pin "2") (pinfunction "VIN_2") (pintype "bidirectional"))
      (node (ref "PALPATINE-12V") (pin "1") (pinfunction "+VIN_1") (pintype "bidirectional"))
      (node (ref "Q1") (pin "1") (pinfunction "IP+_1") (pintype "bidirectional"))
      (node (ref "R3") (pin "2") (pinfunction "2_2") (pintype "passive"))
      (node (ref "SIDEOUS-12V") (pin "1") (pinfunction "+VIN_1") (pintype "bidirectional"))
      (node (ref "U$14") (pin "1") (pinfunction "IP+_1") (pintype "bidirectional"))
      (node (ref "U$15") (pin "1") (pinfunction "IP+_1") (pintype "bidirectional"))
      (node (ref "U$16") (pin "1") (pinfunction "IP+_1") (pintype "bidirectional"))
      (node (ref "U$17") (pin "1") (pinfunction "IP+_1") (pintype "bidirectional"))
      (node (ref "U$18") (pin "1") (pinfunction "IP+_1") (pintype "bidirectional"))
      (node (ref "U$19") (pin "1") (pinfunction "IP+_1") (pintype "bidirectional"))
      (node (ref "U$20") (pin "1") (pinfunction "IP+_1") (pintype "bidirectional"))
      (node (ref "VADER-5V-EXT") (pin "2") (pinfunction "VIN_2") (pintype "bidirectional"))
    )
    (net (code "91") (name "unconnected-(DOOKU-12V-CRIT-INHIBIT-Pad3)") (class "Default")
      (node (ref "DOOKU-12V-CRIT") (pin "3") (pinfunction "INHIBIT_3") (pintype "bidirectional"))
    )
    (net (code "92") (name "unconnected-(Q1-FAULT-Pad6)") (class "Default")
      (node (ref "Q1") (pin "6") (pinfunction "FAULT_6") (pintype "bidirectional"))
    )
    (net (code "93") (name "unconnected-(Q4-FAULT-Pad6)") (class "Default")
      (node (ref "Q4") (pin "6") (pinfunction "FAULT_6") (pintype "bidirectional"))
    )
    (net (code "94") (name "unconnected-(Q5-FAULT-Pad6)") (class "Default")
      (node (ref "Q5") (pin "6") (pinfunction "FAULT_6") (pintype "bidirectional"))
    )
    (net (code "95") (name "unconnected-(U$1-AREF-Pad18)") (class "Default")
      (node (ref "U$1") (pin "18") (pinfunction "AREF_18") (pintype "bidirectional"))
    )
    (net (code "96") (name "unconnected-(U$1-RST-Pad7)") (class "Default")
      (node (ref "U$1") (pin "7") (pinfunction "RST_7") (pintype "bidirectional"))
    )
    (net (code "97") (name "unconnected-(U$1-VBUS-Pad16)") (class "Default")
      (node (ref "U$1") (pin "16") (pinfunction "VBUS_16") (pintype "bidirectional"))
    )
    (net (code "98") (name "unconnected-(U$4-Pad4)") (class "Default")
      (node (ref "U$4") (pin "4") (pinfunction "4_4") (pintype "bidirectional"))
    )
    (net (code "99") (name "unconnected-(U$4-Pad5)") (class "Default")
      (node (ref "U$4") (pin "5") (pinfunction "5_5") (pintype "bidirectional"))
    )
    (net (code "100") (name "unconnected-(U$6-FAULT-Pad3)") (class "Default")
      (node (ref "U$6") (pin "3") (pinfunction "FAULT_3") (pintype "bidirectional"))
    )
    (net (code "101") (name "unconnected-(U$6-TIMER-Pad2)") (class "Default")
      (node (ref "U$6") (pin "2") (pinfunction "TIMER_2") (pintype "bidirectional"))
    )
    (net (code "102") (name "unconnected-(U$7-FAULT-Pad3)") (class "Default")
      (node (ref "U$7") (pin "3") (pinfunction "FAULT_3") (pintype "bidirectional"))
    )
    (net (code "103") (name "unconnected-(U$7-TIMER-Pad2)") (class "Default")
      (node (ref "U$7") (pin "2") (pinfunction "TIMER_2") (pintype "bidirectional"))
    )
    (net (code "104") (name "unconnected-(U$8-FAULT-Pad3)") (class "Default")
      (node (ref "U$8") (pin "3") (pinfunction "FAULT_3") (pintype "bidirectional"))
    )
    (net (code "105") (name "unconnected-(U$8-TIMER-Pad2)") (class "Default")
      (node (ref "U$8") (pin "2") (pinfunction "TIMER_2") (pintype "bidirectional"))
    )
    (net (code "106") (name "unconnected-(U$9-FAULT-Pad3)") (class "Default")
      (node (ref "U$9") (pin "3") (pinfunction "FAULT_3") (pintype "bidirectional"))
    )
    (net (code "107") (name "unconnected-(U$9-TIMER-Pad2)") (class "Default")
      (node (ref "U$9") (pin "2") (pinfunction "TIMER_2") (pintype "bidirectional"))
    )
    (net (code "108") (name "unconnected-(U$10-FAULT-Pad3)") (class "Default")
      (node (ref "U$10") (pin "3") (pinfunction "FAULT_3") (pintype "bidirectional"))
    )
    (net (code "109") (name "unconnected-(U$10-TIMER-Pad2)") (class "Default")
      (node (ref "U$10") (pin "2") (pinfunction "TIMER_2") (pintype "bidirectional"))
    )
    (net (code "110") (name "unconnected-(U$11-FAULT-Pad3)") (class "Default")
      (node (ref "U$11") (pin "3") (pinfunction "FAULT_3") (pintype "bidirectional"))
    )
    (net (code "111") (name "unconnected-(U$11-TIMER-Pad2)") (class "Default")
      (node (ref "U$11") (pin "2") (pinfunction "TIMER_2") (pintype "bidirectional"))
    )
    (net (code "112") (name "unconnected-(U$12-FAULT-Pad3)") (class "Default")
      (node (ref "U$12") (pin "3") (pinfunction "FAULT_3") (pintype "bidirectional"))
    )
    (net (code "113") (name "unconnected-(U$12-TIMER-Pad2)") (class "Default")
      (node (ref "U$12") (pin "2") (pinfunction "TIMER_2") (pintype "bidirectional"))
    )
    (net (code "114") (name "unconnected-(U$13-FAULT-Pad3)") (class "Default")
      (node (ref "U$13") (pin "3") (pinfunction "FAULT_3") (pintype "bidirectional"))
    )
    (net (code "115") (name "unconnected-(U$13-TIMER-Pad2)") (class "Default")
      (node (ref "U$13") (pin "2") (pinfunction "TIMER_2") (pintype "bidirectional"))
    )
    (net (code "116") (name "unconnected-(VADER-5V-EXT-INHIBIT-Pad3)") (class "Default")
      (node (ref "VADER-5V-EXT") (pin "3") (pinfunction "INHIBIT_3") (pintype "bidirectional"))
    )
  )
)
